# axiom_beta_plugin_module_TE0714_SDI_v0_8.net
KiCad netlist of a schematic drawn in EAGLE
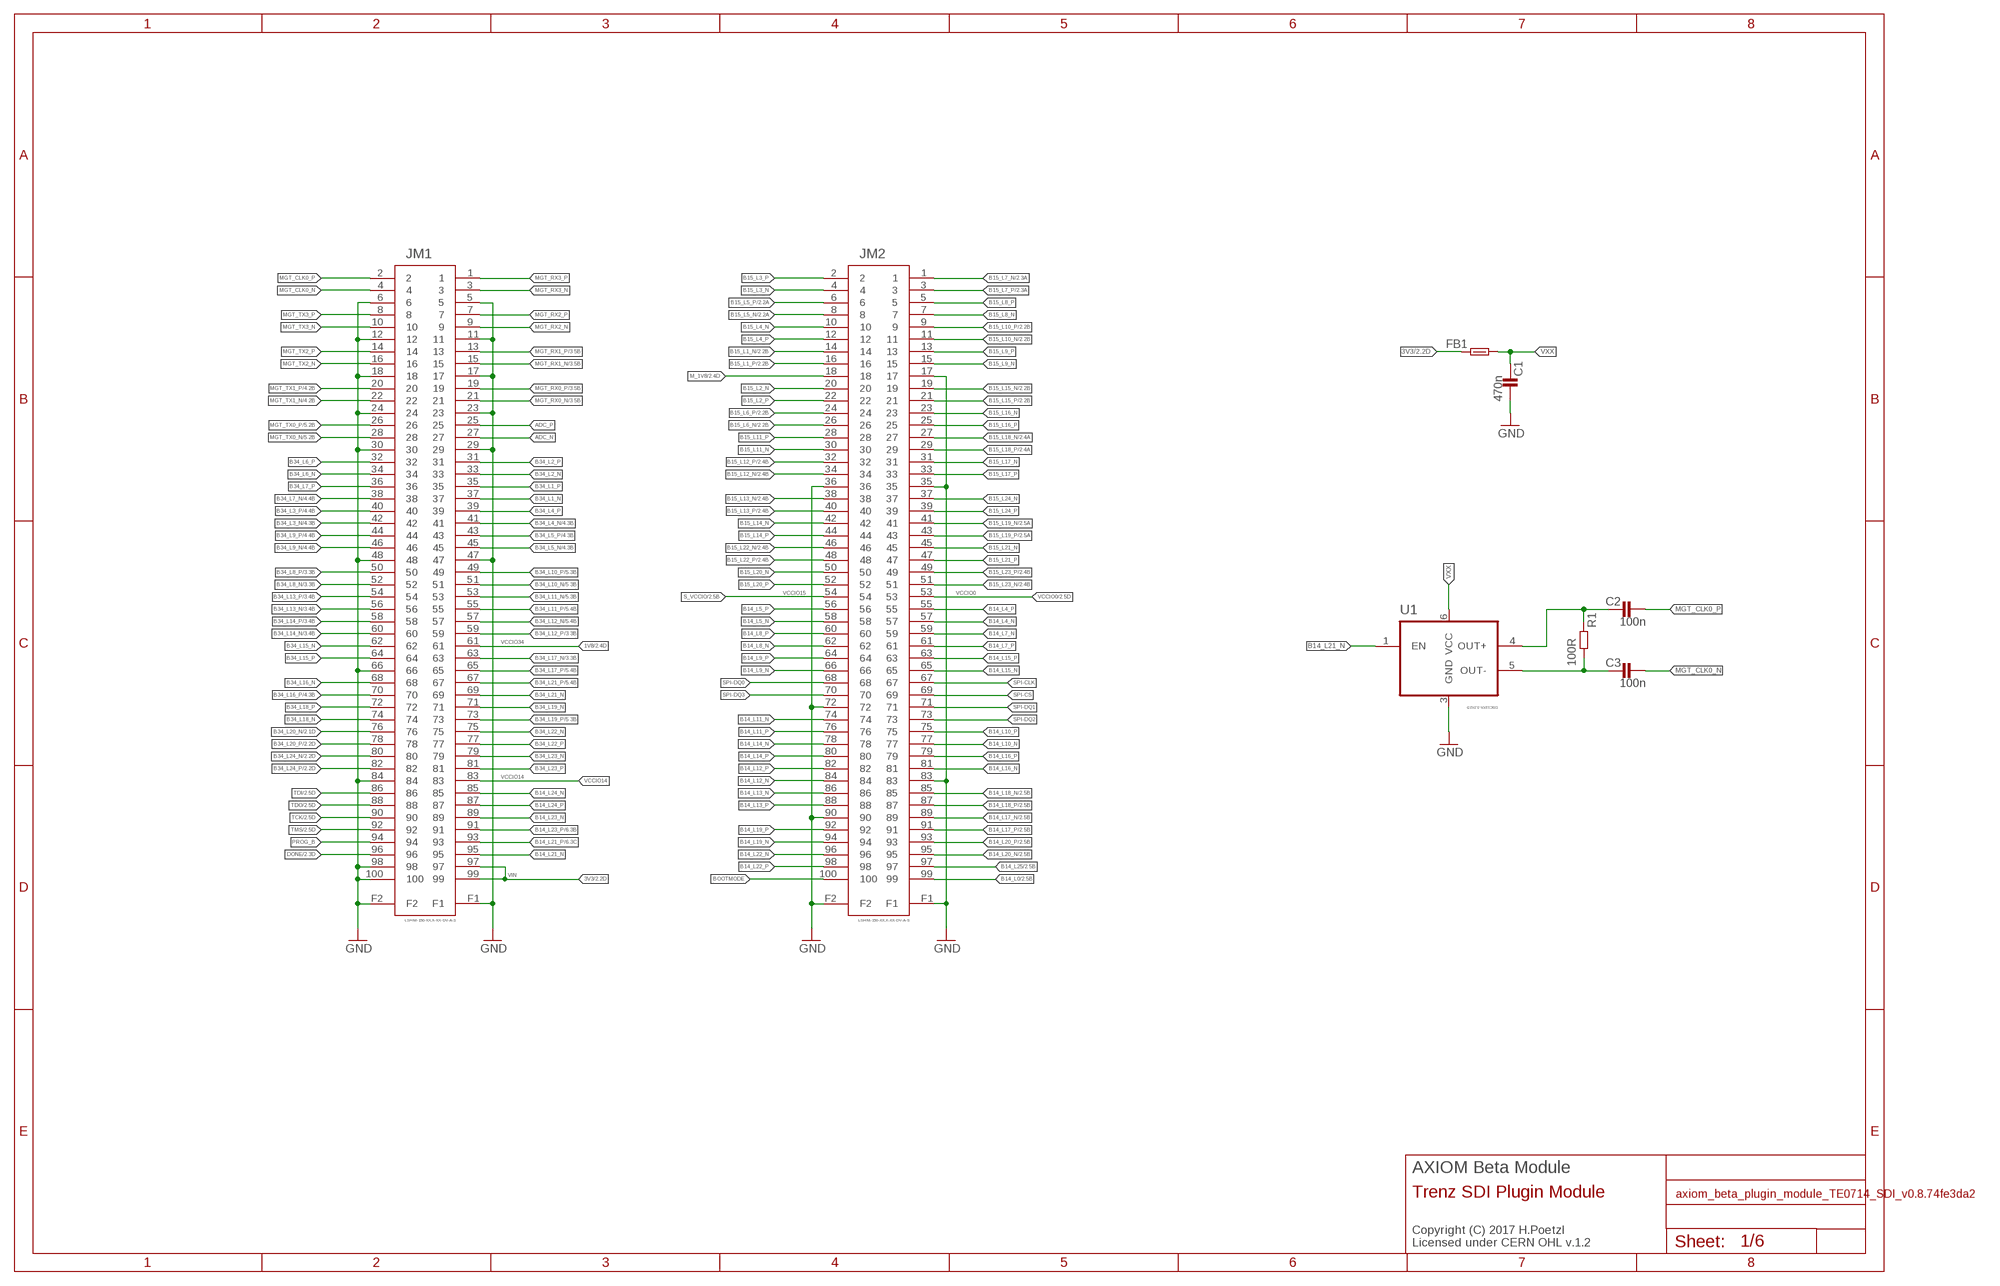
[diagram p0: schematic, sheet 1]
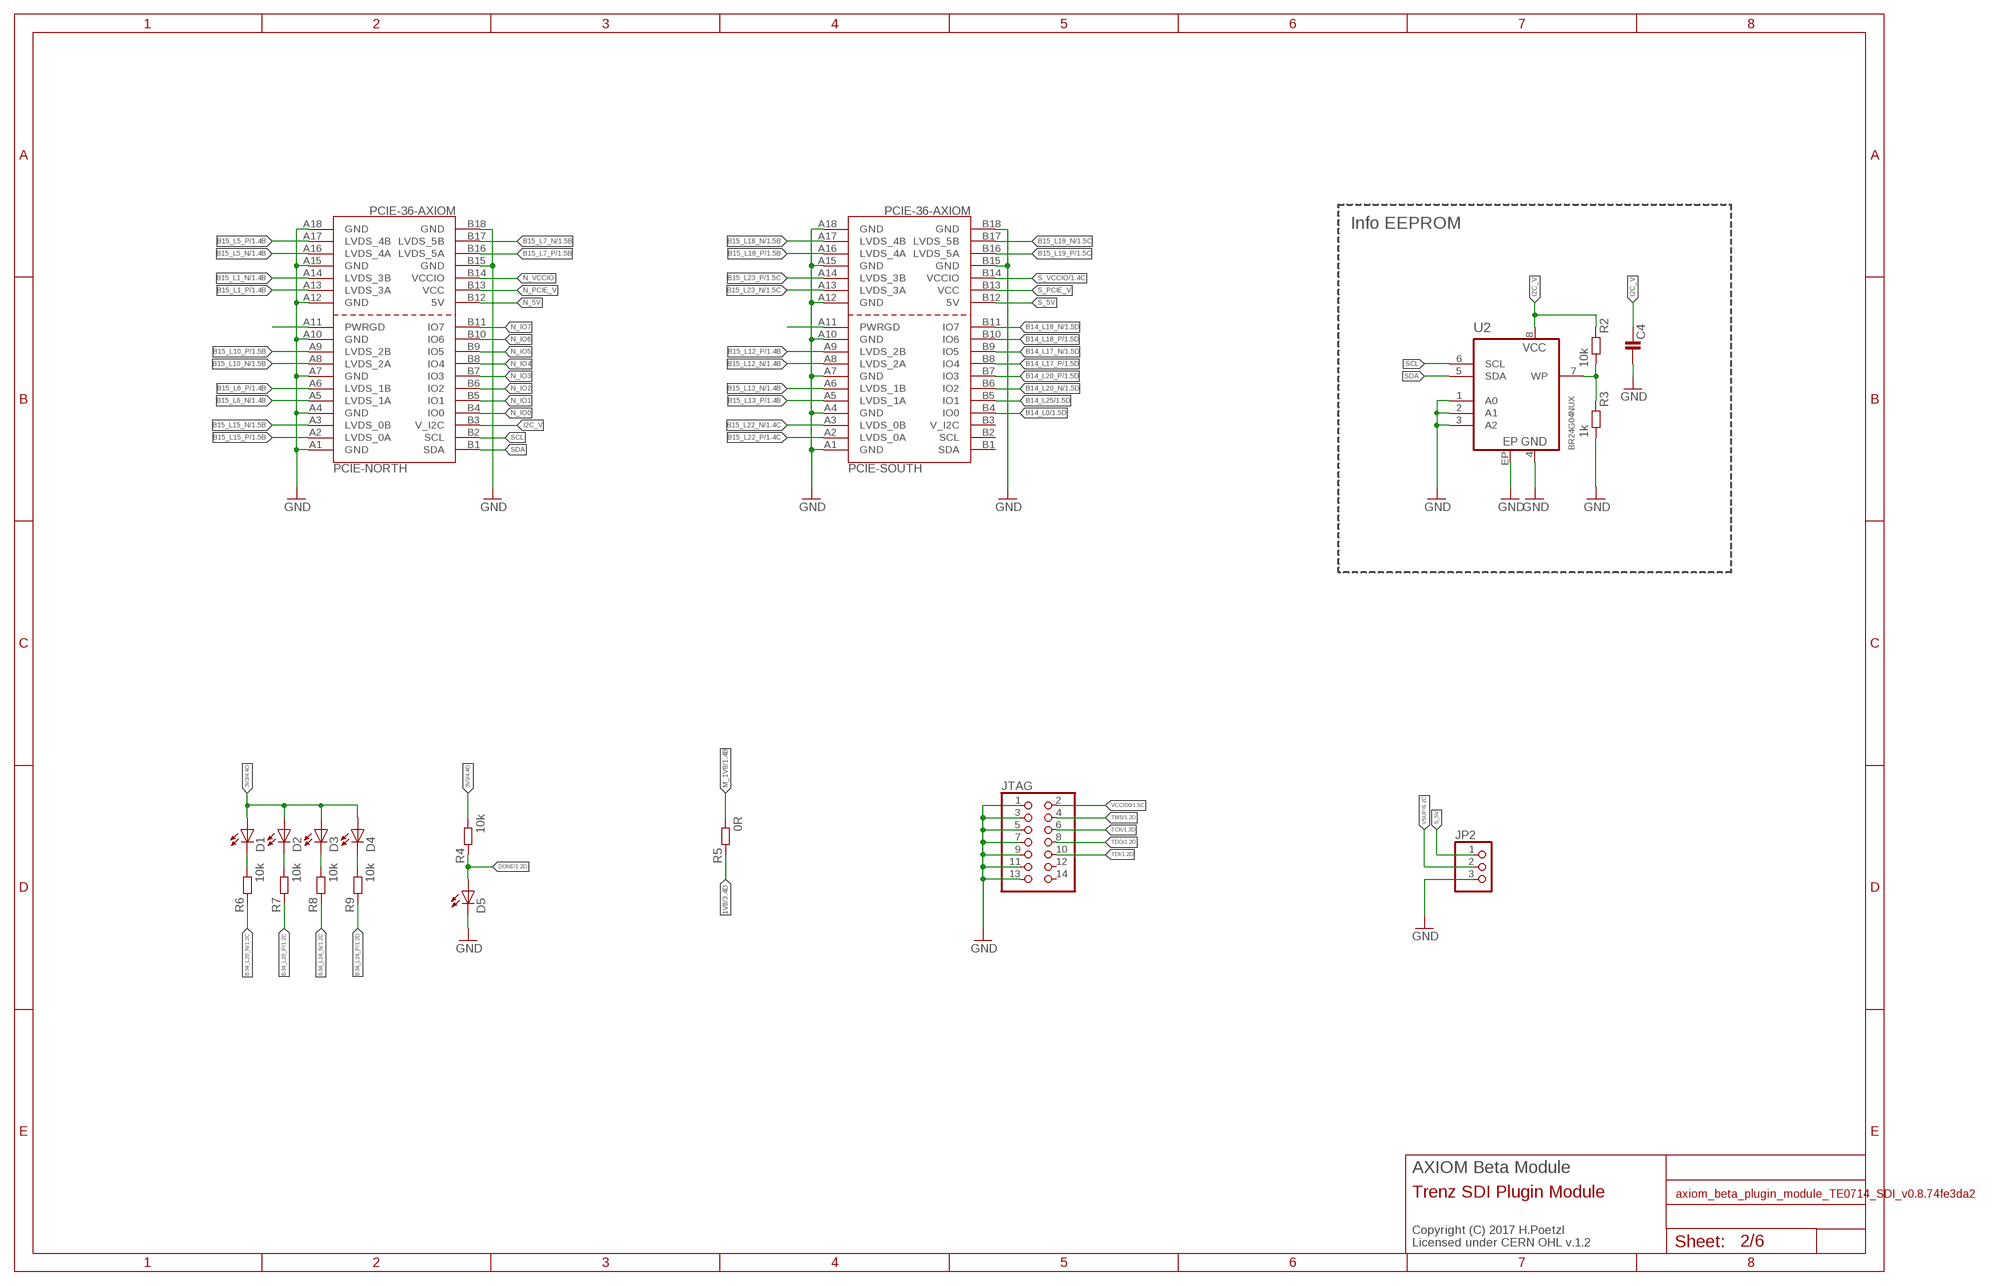
[diagram p1: schematic, sheet 2]
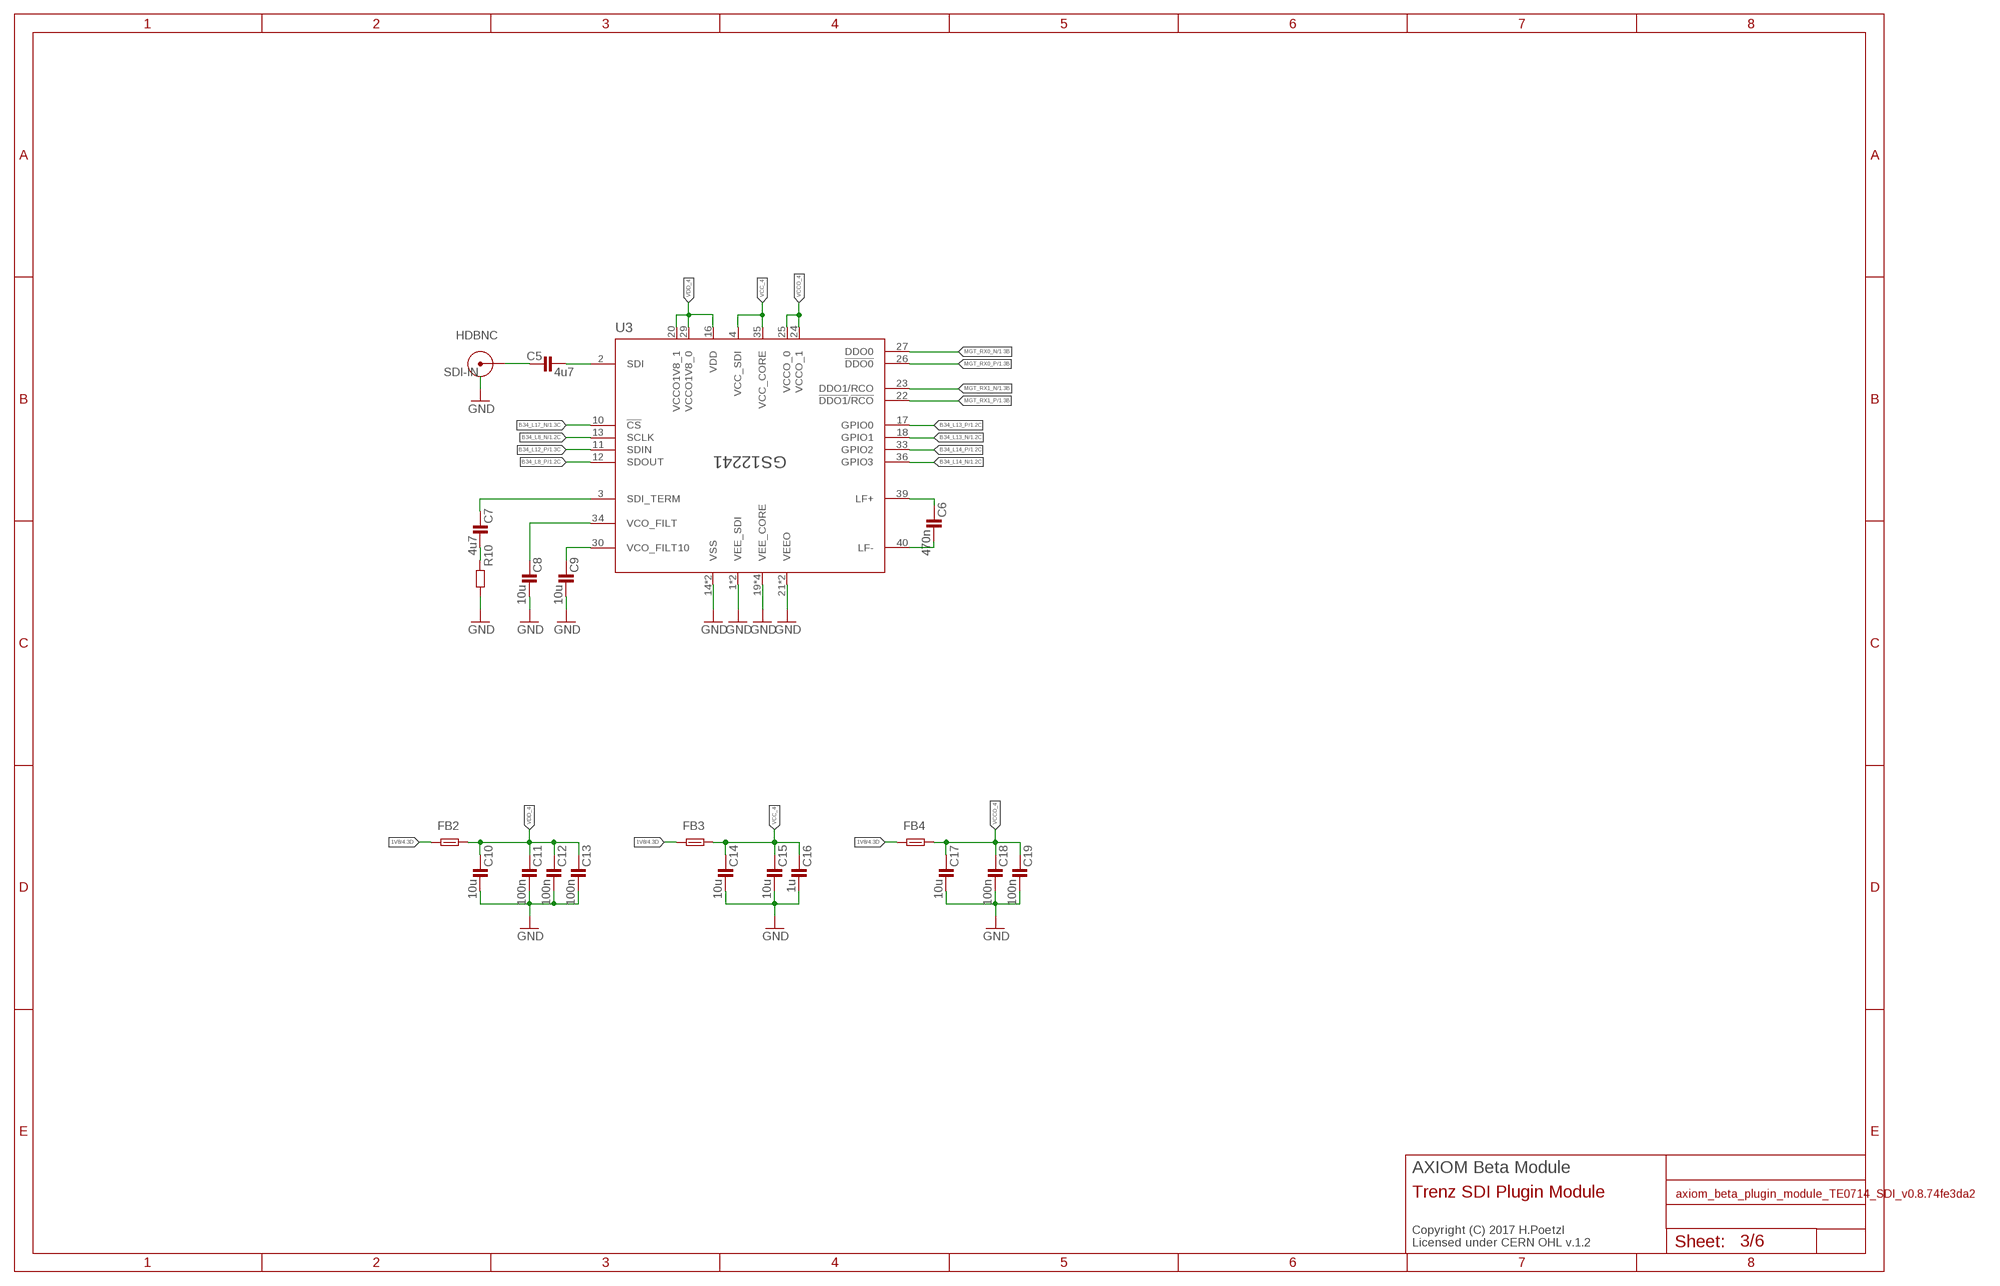
[diagram p2: schematic, sheet 3]
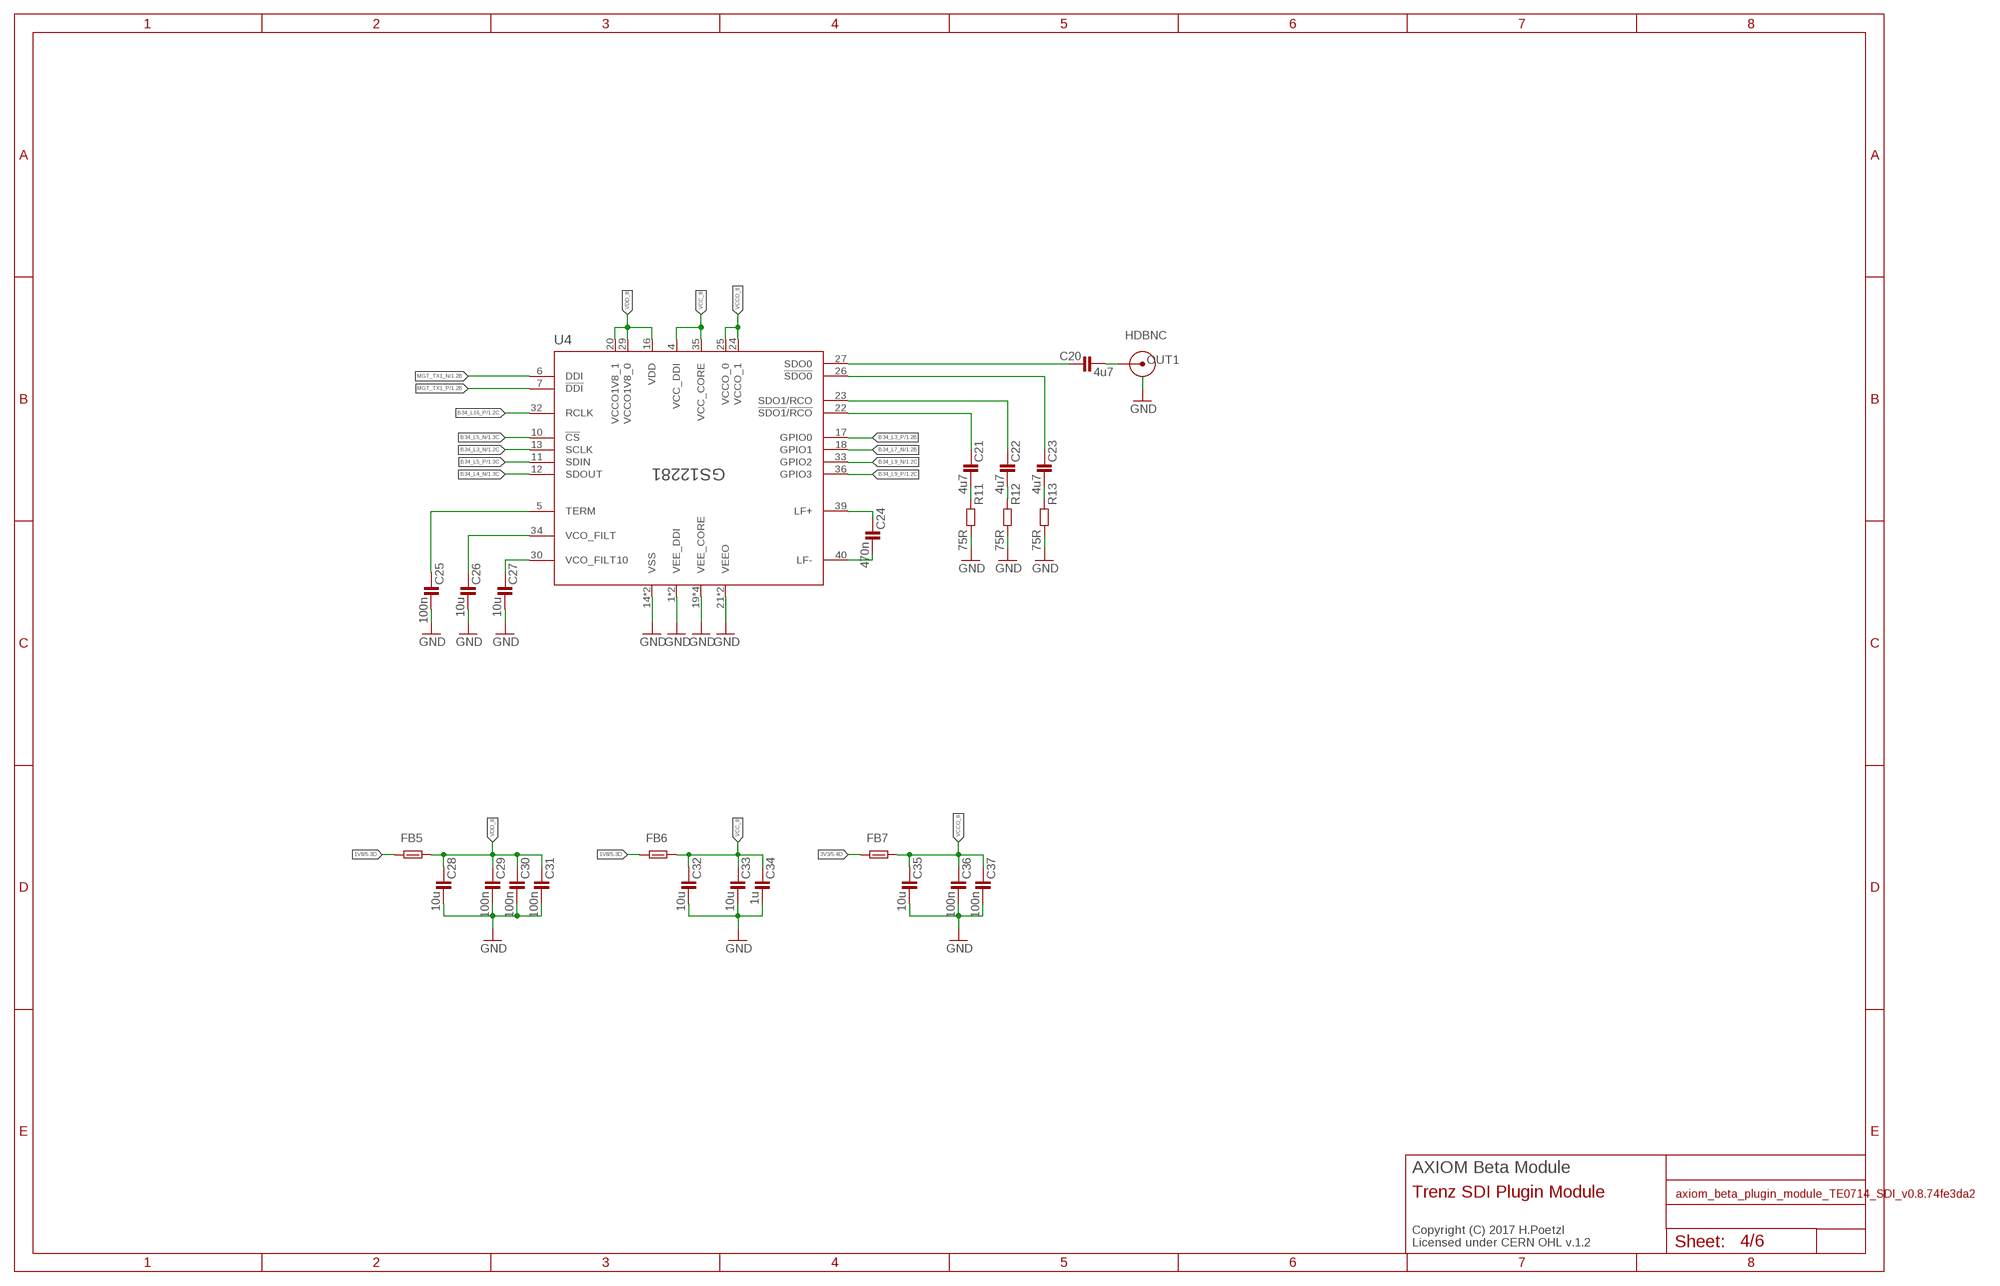
[diagram p3: schematic, sheet 4]
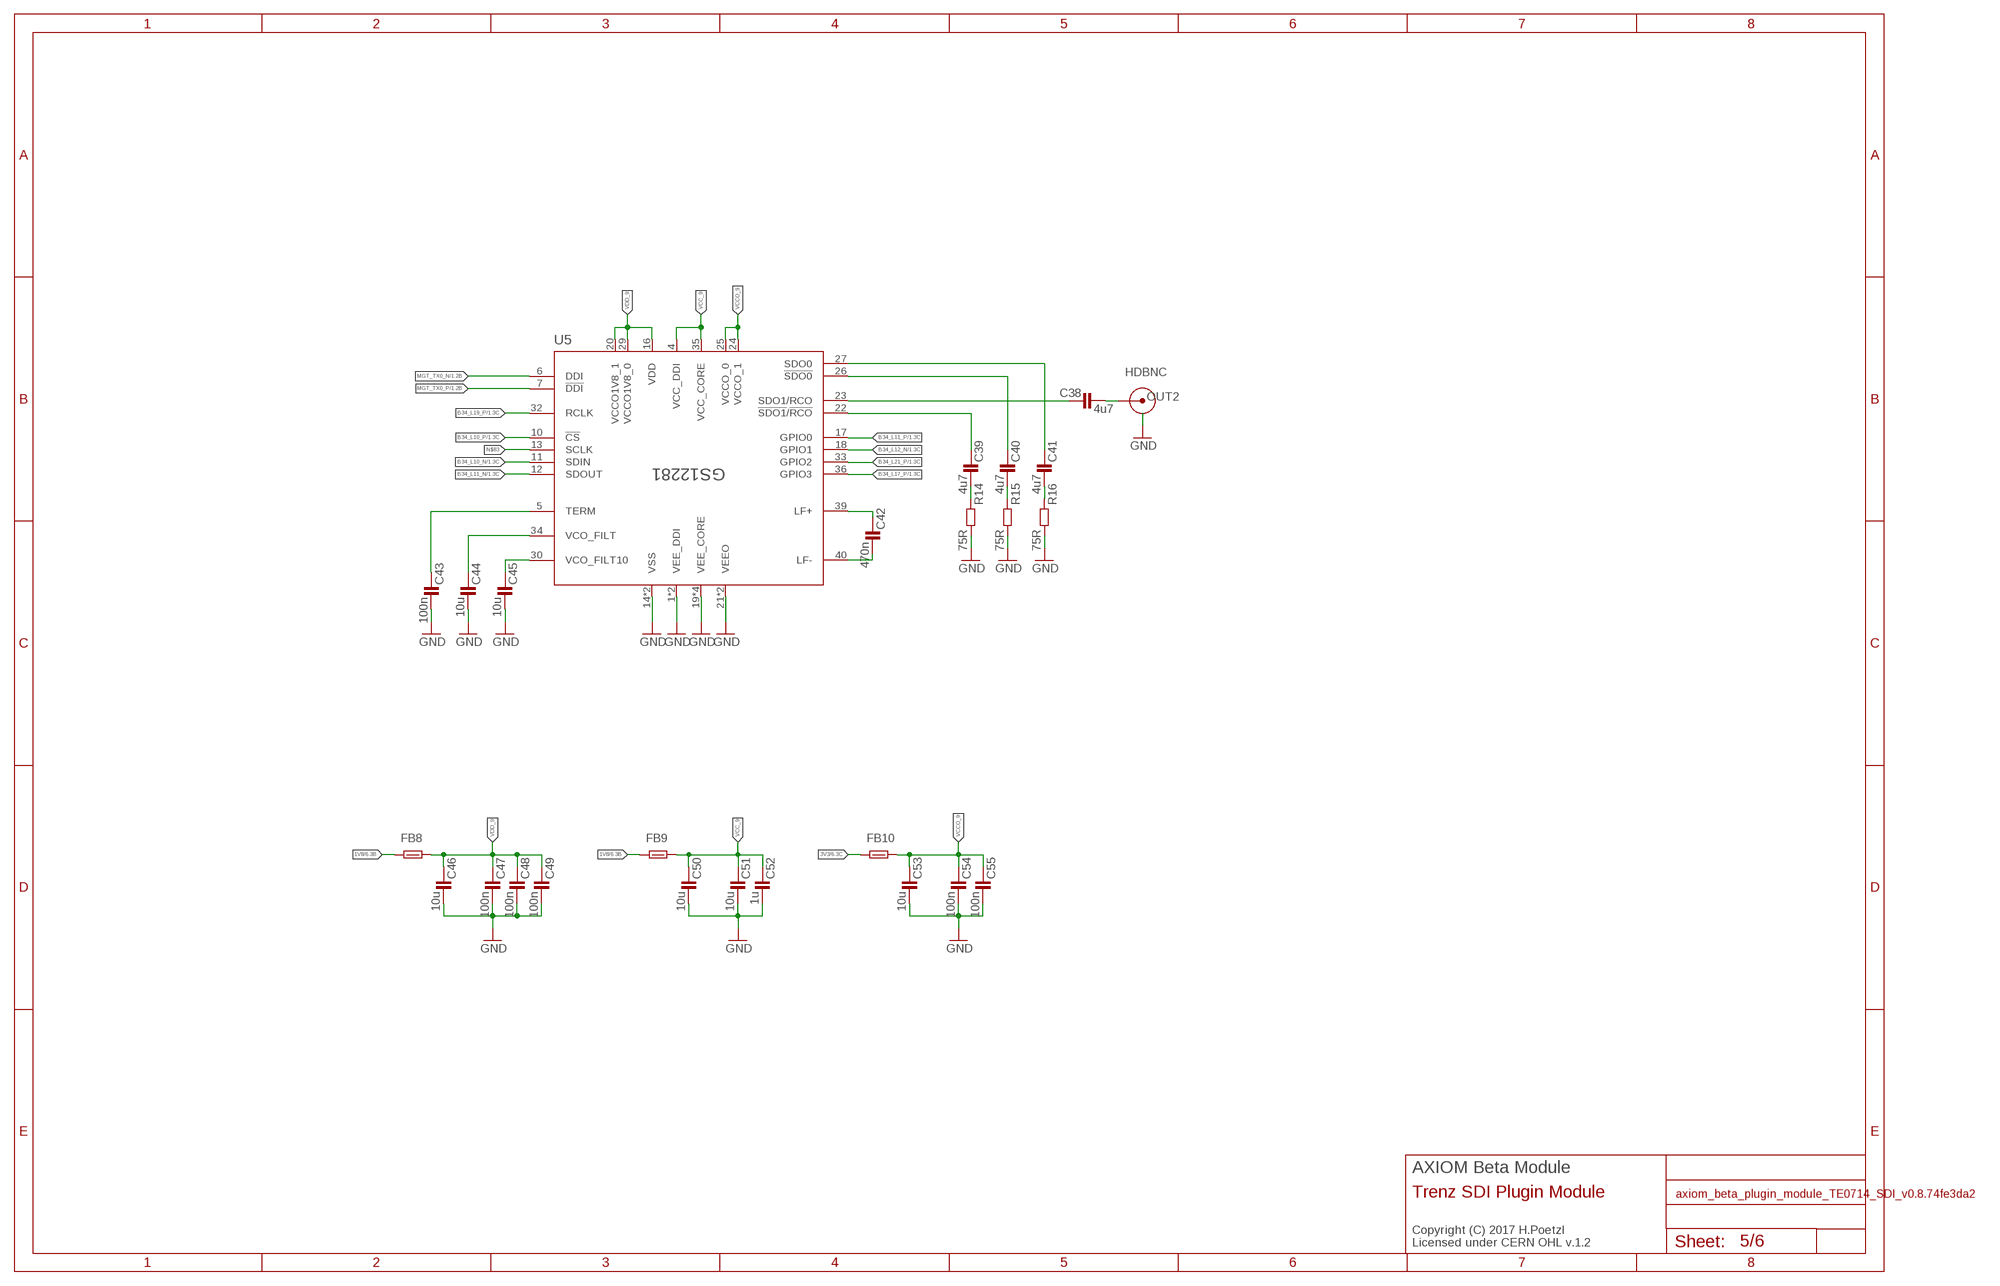
[diagram p4: schematic, sheet 5]
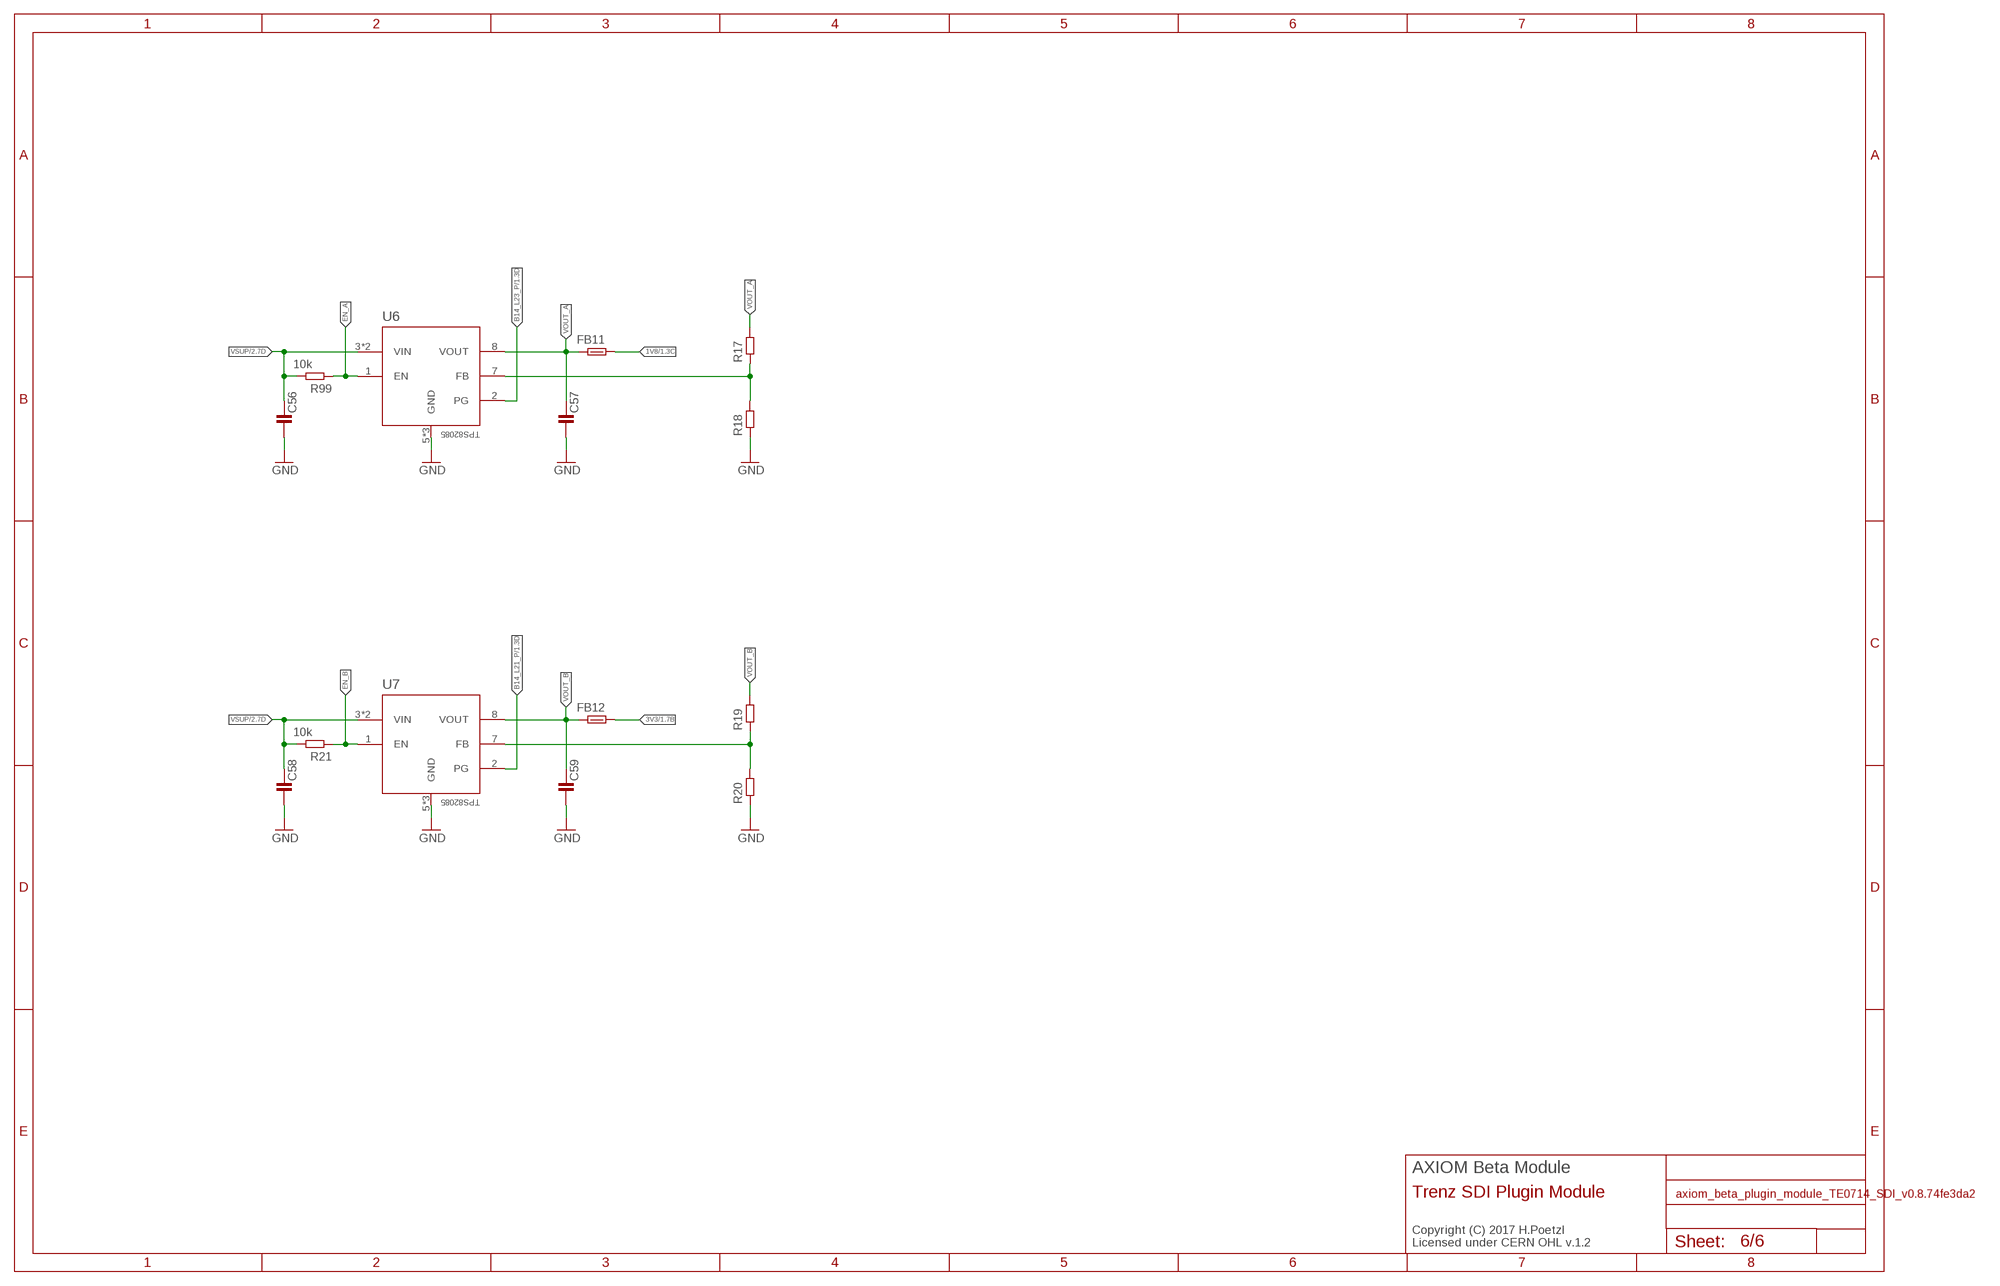
[diagram p5: schematic, sheet 6]

(export (version "E")
  (design (tool "Eeschema 10.0.6"))
  (components
    (comp (ref "C38")
      (value "4u7")
      (footprint "eagle-import:0402-C")
      (libsource (lib "eagle-import") (part "C0402-C"))
    )
    (comp (ref "C39")
      (value "4u7")
      (footprint "eagle-import:0402-C")
      (libsource (lib "eagle-import") (part "C0402-C"))
    )
    (comp (ref "C40")
      (value "4u7")
      (footprint "eagle-import:0402-C")
      (libsource (lib "eagle-import") (part "C0402-C"))
    )
    (comp (ref "C41")
      (value "4u7")
      (footprint "eagle-import:0402-C")
      (libsource (lib "eagle-import") (part "C0402-C"))
    )
    (comp (ref "C42")
      (value "470n")
      (footprint "eagle-import:0201-C")
      (libsource (lib "eagle-import") (part "C0201-C"))
    )
    (comp (ref "C43")
      (value "100n")
      (footprint "eagle-import:0201-C")
      (libsource (lib "eagle-import") (part "C0201-C"))
    )
    (comp (ref "C44")
      (value "10u")
      (footprint "eagle-import:0402-C")
      (libsource (lib "eagle-import") (part "C0402-C"))
    )
    (comp (ref "C45")
      (value "10u")
      (footprint "eagle-import:0402-C")
      (libsource (lib "eagle-import") (part "C0402-C"))
    )
    (comp (ref "C46")
      (value "10u")
      (footprint "eagle-import:0402-C")
      (libsource (lib "eagle-import") (part "C0402-C"))
    )
    (comp (ref "C47")
      (value "100n")
      (footprint "eagle-import:0201-C")
      (libsource (lib "eagle-import") (part "C0201-C"))
    )
    (comp (ref "C48")
      (value "100n")
      (footprint "eagle-import:0201-C")
      (libsource (lib "eagle-import") (part "C0201-C"))
    )
    (comp (ref "C49")
      (value "100n")
      (footprint "eagle-import:0201-C")
      (libsource (lib "eagle-import") (part "C0201-C"))
    )
    (comp (ref "C50")
      (value "10u")
      (footprint "eagle-import:0402-C")
      (libsource (lib "eagle-import") (part "C0402-C"))
    )
    (comp (ref "C51")
      (value "10u")
      (footprint "eagle-import:0402-C")
      (libsource (lib "eagle-import") (part "C0402-C"))
    )
    (comp (ref "C52")
      (value "1u")
      (footprint "eagle-import:0201-C")
      (libsource (lib "eagle-import") (part "C0201-C"))
    )
    (comp (ref "C53")
      (value "10u")
      (footprint "eagle-import:0402-C")
      (libsource (lib "eagle-import") (part "C0402-C"))
    )
    (comp (ref "C54")
      (value "100n")
      (footprint "eagle-import:0201-C")
      (libsource (lib "eagle-import") (part "C0201-C"))
    )
    (comp (ref "C55")
      (value "100n")
      (footprint "eagle-import:0201-C")
      (libsource (lib "eagle-import") (part "C0201-C"))
    )
    (comp (ref "FB8")
      (value "FB0402-C")
      (footprint "eagle-import:0402-C")
      (libsource (lib "eagle-import") (part "FB0402-C"))
    )
    (comp (ref "FB9")
      (value "FB0402-C")
      (footprint "eagle-import:0402-C")
      (libsource (lib "eagle-import") (part "FB0402-C"))
    )
    (comp (ref "FB10")
      (value "FB0402-C")
      (footprint "eagle-import:0402-C")
      (libsource (lib "eagle-import") (part "FB0402-C"))
    )
    (comp (ref "OUT2")
      (value "HDBNC")
      (footprint "eagle-import:HDBNC_EDGE_2SIDE")
      (libsource (lib "eagle-import") (part "HDBNC"))
    )
    (comp (ref "R14")
      (value "75R")
      (footprint "eagle-import:0201-C")
      (libsource (lib "eagle-import") (part "R0201-C"))
    )
    (comp (ref "R15")
      (value "75R")
      (footprint "eagle-import:0201-C")
      (libsource (lib "eagle-import") (part "R0201-C"))
    )
    (comp (ref "R16")
      (value "75R")
      (footprint "eagle-import:0201-C")
      (libsource (lib "eagle-import") (part "R0201-C"))
    )
    (comp (ref "U5")
      (value "GS12281")
      (footprint "eagle-import:UQFN40P600X400X100-41N")
      (libsource (lib "eagle-import") (part "GS12281"))
    )
    (comp (ref "C4")
      (value "C0402-B")
      (footprint "eagle-import:0402-B")
      (libsource (lib "eagle-import") (part "C0402-B"))
    )
    (comp (ref "D1")
      (value "LED")
      (footprint "eagle-import:CHIPLED_0603")
      (libsource (lib "eagle-import") (part "LED"))
    )
    (comp (ref "D2")
      (value "LED")
      (footprint "eagle-import:CHIPLED_0603")
      (libsource (lib "eagle-import") (part "LED"))
    )
    (comp (ref "D3")
      (value "LED")
      (footprint "eagle-import:CHIPLED_0603")
      (libsource (lib "eagle-import") (part "LED"))
    )
    (comp (ref "D4")
      (value "LED")
      (footprint "eagle-import:CHIPLED_0603")
      (libsource (lib "eagle-import") (part "LED"))
    )
    (comp (ref "D5")
      (value "LED")
      (footprint "eagle-import:CHIPLED_0603")
      (libsource (lib "eagle-import") (part "LED"))
    )
    (comp (ref "JP2")
      (value "PINHD-1X03_2.54-90°-S")
      (footprint "eagle-import:1X03_90-S")
      (libsource (lib "eagle-import") (part "PINHD-1X03_2.54-90°-S"))
    )
    (comp (ref "JTAG")
      (value "PINHD-2X07_2.00")
      (footprint "eagle-import:2X07M")
      (libsource (lib "eagle-import") (part "PINHD-2X07_2.00"))
    )
    (comp (ref "PCIE-NORTH")
      (value "PCIE-36-AXIOM")
      (footprint "eagle-import:PCIE-36-AXIOM")
      (libsource (lib "eagle-import") (part "PCIE-36-AXIOM"))
    )
    (comp (ref "PCIE-SOUTH")
      (value "PCIE-36-AXIOM")
      (footprint "eagle-import:PCIE-36-AXIOM")
      (libsource (lib "eagle-import") (part "PCIE-36-AXIOM"))
    )
    (comp (ref "R2")
      (value "10k")
      (footprint "eagle-import:0402-B")
      (libsource (lib "eagle-import") (part "R0402-B"))
    )
    (comp (ref "R3")
      (value "1k")
      (footprint "eagle-import:0402-B")
      (libsource (lib "eagle-import") (part "R0402-B"))
    )
    (comp (ref "R4")
      (value "10k")
      (footprint "eagle-import:0402-C")
      (libsource (lib "eagle-import") (part "R0402-C"))
    )
    (comp (ref "R5")
      (value "0R")
      (footprint "eagle-import:0402-C")
      (libsource (lib "eagle-import") (part "R0402-C"))
    )
    (comp (ref "R6")
      (value "10k")
      (footprint "eagle-import:0402-C")
      (libsource (lib "eagle-import") (part "R0402-C"))
    )
    (comp (ref "R7")
      (value "10k")
      (footprint "eagle-import:0402-C")
      (libsource (lib "eagle-import") (part "R0402-C"))
    )
    (comp (ref "R8")
      (value "10k")
      (footprint "eagle-import:0402-C")
      (libsource (lib "eagle-import") (part "R0402-C"))
    )
    (comp (ref "R9")
      (value "10k")
      (footprint "eagle-import:0402-C")
      (libsource (lib "eagle-import") (part "R0402-C"))
    )
    (comp (ref "U2")
      (value "BR24G04NUX")
      (footprint "eagle-import:DFN200X300X100-9N")
      (libsource (lib "eagle-import") (part "BR24G04NUX"))
    )
    (comp (ref "C5")
      (value "4u7")
      (footprint "eagle-import:0402-C")
      (libsource (lib "eagle-import") (part "C0402-C"))
    )
    (comp (ref "C6")
      (value "470n")
      (footprint "eagle-import:0201-C")
      (libsource (lib "eagle-import") (part "C0201-C"))
    )
    (comp (ref "C7")
      (value "4u7")
      (footprint "eagle-import:0402-C")
      (libsource (lib "eagle-import") (part "C0402-C"))
    )
    (comp (ref "C8")
      (value "10u")
      (footprint "eagle-import:0201-C")
      (libsource (lib "eagle-import") (part "C0201-C"))
    )
    (comp (ref "C9")
      (value "10u")
      (footprint "eagle-import:0402-C")
      (libsource (lib "eagle-import") (part "C0402-C"))
    )
    (comp (ref "C10")
      (value "10u")
      (footprint "eagle-import:0402-C")
      (libsource (lib "eagle-import") (part "C0402-C"))
    )
    (comp (ref "C11")
      (value "100n")
      (footprint "eagle-import:0201-C")
      (libsource (lib "eagle-import") (part "C0201-C"))
    )
    (comp (ref "C12")
      (value "100n")
      (footprint "eagle-import:0201-C")
      (libsource (lib "eagle-import") (part "C0201-C"))
    )
    (comp (ref "C13")
      (value "100n")
      (footprint "eagle-import:0201-C")
      (libsource (lib "eagle-import") (part "C0201-C"))
    )
    (comp (ref "C14")
      (value "10u")
      (footprint "eagle-import:0402-C")
      (libsource (lib "eagle-import") (part "C0402-C"))
    )
    (comp (ref "C15")
      (value "10u")
      (footprint "eagle-import:0402-C")
      (libsource (lib "eagle-import") (part "C0402-C"))
    )
    (comp (ref "C16")
      (value "1u")
      (footprint "eagle-import:0201-C")
      (libsource (lib "eagle-import") (part "C0201-C"))
    )
    (comp (ref "C17")
      (value "10u")
      (footprint "eagle-import:0402-C")
      (libsource (lib "eagle-import") (part "C0402-C"))
    )
    (comp (ref "C18")
      (value "100n")
      (footprint "eagle-import:0201-C")
      (libsource (lib "eagle-import") (part "C0201-C"))
    )
    (comp (ref "C19")
      (value "100n")
      (footprint "eagle-import:0201-C")
      (libsource (lib "eagle-import") (part "C0201-C"))
    )
    (comp (ref "FB2")
      (value "FB0402-C")
      (footprint "eagle-import:0402-C")
      (libsource (lib "eagle-import") (part "FB0402-C"))
    )
    (comp (ref "FB3")
      (value "FB0402-C")
      (footprint "eagle-import:0402-C")
      (libsource (lib "eagle-import") (part "FB0402-C"))
    )
    (comp (ref "FB4")
      (value "FB0402-C")
      (footprint "eagle-import:0402-C")
      (libsource (lib "eagle-import") (part "FB0402-C"))
    )
    (comp (ref "R10")
      (value "R0201-C")
      (footprint "eagle-import:0201-C")
      (libsource (lib "eagle-import") (part "R0201-C"))
    )
    (comp (ref "SDI-IN")
      (value "HDBNC")
      (footprint "eagle-import:HDBNC_EDGE_2SIDE")
      (libsource (lib "eagle-import") (part "HDBNC"))
    )
    (comp (ref "U3")
      (value "GS12241")
      (footprint "eagle-import:UQFN40P600X400X100-41N")
      (libsource (lib "eagle-import") (part "GS12241"))
    )
    (comp (ref "C20")
      (value "4u7")
      (footprint "eagle-import:0402-C")
      (libsource (lib "eagle-import") (part "C0402-C"))
    )
    (comp (ref "C21")
      (value "4u7")
      (footprint "eagle-import:0402-C")
      (libsource (lib "eagle-import") (part "C0402-C"))
    )
    (comp (ref "C22")
      (value "4u7")
      (footprint "eagle-import:0402-C")
      (libsource (lib "eagle-import") (part "C0402-C"))
    )
    (comp (ref "C23")
      (value "4u7")
      (footprint "eagle-import:0402-C")
      (libsource (lib "eagle-import") (part "C0402-C"))
    )
    (comp (ref "C24")
      (value "470n")
      (footprint "eagle-import:0201-C")
      (libsource (lib "eagle-import") (part "C0201-C"))
    )
    (comp (ref "C25")
      (value "100n")
      (footprint "eagle-import:0201-C")
      (libsource (lib "eagle-import") (part "C0201-C"))
    )
    (comp (ref "C26")
      (value "10u")
      (footprint "eagle-import:0201-C")
      (libsource (lib "eagle-import") (part "C0201-C"))
    )
    (comp (ref "C27")
      (value "10u")
      (footprint "eagle-import:0402-C")
      (libsource (lib "eagle-import") (part "C0402-C"))
    )
    (comp (ref "C28")
      (value "10u")
      (footprint "eagle-import:0402-C")
      (libsource (lib "eagle-import") (part "C0402-C"))
    )
    (comp (ref "C29")
      (value "100n")
      (footprint "eagle-import:0201-C")
      (libsource (lib "eagle-import") (part "C0201-C"))
    )
    (comp (ref "C30")
      (value "100n")
      (footprint "eagle-import:0201-C")
      (libsource (lib "eagle-import") (part "C0201-C"))
    )
    (comp (ref "C31")
      (value "100n")
      (footprint "eagle-import:0201-C")
      (libsource (lib "eagle-import") (part "C0201-C"))
    )
    (comp (ref "C32")
      (value "10u")
      (footprint "eagle-import:0402-C")
      (libsource (lib "eagle-import") (part "C0402-C"))
    )
    (comp (ref "C33")
      (value "10u")
      (footprint "eagle-import:0402-C")
      (libsource (lib "eagle-import") (part "C0402-C"))
    )
    (comp (ref "C34")
      (value "1u")
      (footprint "eagle-import:0201-C")
      (libsource (lib "eagle-import") (part "C0201-C"))
    )
    (comp (ref "C35")
      (value "10u")
      (footprint "eagle-import:0402-C")
      (libsource (lib "eagle-import") (part "C0402-C"))
    )
    (comp (ref "C36")
      (value "100n")
      (footprint "eagle-import:0201-C")
      (libsource (lib "eagle-import") (part "C0201-C"))
    )
    (comp (ref "C37")
      (value "100n")
      (footprint "eagle-import:0201-C")
      (libsource (lib "eagle-import") (part "C0201-C"))
    )
    (comp (ref "FB5")
      (value "FB0402-C")
      (footprint "eagle-import:0402-C")
      (libsource (lib "eagle-import") (part "FB0402-C"))
    )
    (comp (ref "FB6")
      (value "FB0402-C")
      (footprint "eagle-import:0402-C")
      (libsource (lib "eagle-import") (part "FB0402-C"))
    )
    (comp (ref "FB7")
      (value "FB0402-C")
      (footprint "eagle-import:0402-C")
      (libsource (lib "eagle-import") (part "FB0402-C"))
    )
    (comp (ref "OUT1")
      (value "HDBNC")
      (footprint "eagle-import:HDBNC_EDGE_2SIDE")
      (libsource (lib "eagle-import") (part "HDBNC"))
    )
    (comp (ref "R11")
      (value "75R")
      (footprint "eagle-import:0201-C")
      (libsource (lib "eagle-import") (part "R0201-C"))
    )
    (comp (ref "R12")
      (value "75R")
      (footprint "eagle-import:0201-C")
      (libsource (lib "eagle-import") (part "R0201-C"))
    )
    (comp (ref "R13")
      (value "75R")
      (footprint "eagle-import:0201-C")
      (libsource (lib "eagle-import") (part "R0201-C"))
    )
    (comp (ref "U4")
      (value "GS12281")
      (footprint "eagle-import:UQFN40P600X400X100-41N")
      (libsource (lib "eagle-import") (part "GS12281"))
    )
    (comp (ref "C1")
      (value "470n")
      (footprint "eagle-import:0402-C")
      (libsource (lib "eagle-import") (part "C0402-C"))
    )
    (comp (ref "C2")
      (value "100n")
      (footprint "eagle-import:0201-C")
      (libsource (lib "eagle-import") (part "C0201-C"))
    )
    (comp (ref "C3")
      (value "100n")
      (footprint "eagle-import:0201-C")
      (libsource (lib "eagle-import") (part "C0201-C"))
    )
    (comp (ref "FB1")
      (value "FB0402-C")
      (footprint "eagle-import:0402-C")
      (libsource (lib "eagle-import") (part "FB0402-C"))
    )
    (comp (ref "JM1")
      (value "LSHM-150-XX.X-XX-DV-A-S")
      (footprint "eagle-import:LSHM-150-XX.X-XX-DV-A-S")
      (libsource (lib "eagle-import") (part "LSHM-150-XX.X-XX-DV-A-S"))
    )
    (comp (ref "JM2")
      (value "LSHM-150-XX.X-XX-DV-A-S")
      (footprint "eagle-import:LSHM-150-XX.X-XX-DV-A-S")
      (libsource (lib "eagle-import") (part "LSHM-150-XX.X-XX-DV-A-S"))
    )
    (comp (ref "R1")
      (value "100R")
      (footprint "eagle-import:0201-C")
      (libsource (lib "eagle-import") (part "R0201-C"))
    )
    (comp (ref "U1")
      (value "DSC11XX-3.2X2.5")
      (footprint "eagle-import:3.2X2.5")
      (libsource (lib "eagle-import") (part "DSC11XX-3.2X2.5"))
    )
    (comp (ref "C56")
      (value "C0603-C")
      (footprint "eagle-import:0603-C")
      (libsource (lib "eagle-import") (part "C0603-C"))
    )
    (comp (ref "C57")
      (value "C0603-C")
      (footprint "eagle-import:0603-C")
      (libsource (lib "eagle-import") (part "C0603-C"))
    )
    (comp (ref "C58")
      (value "C0603-C")
      (footprint "eagle-import:0603-C")
      (libsource (lib "eagle-import") (part "C0603-C"))
    )
    (comp (ref "C59")
      (value "C0603-C")
      (footprint "eagle-import:0603-C")
      (libsource (lib "eagle-import") (part "C0603-C"))
    )
    (comp (ref "FB11")
      (value "FB0603-C")
      (footprint "eagle-import:0603-C")
      (libsource (lib "eagle-import") (part "FB0603-C"))
    )
    (comp (ref "FB12")
      (value "FB0603-C")
      (footprint "eagle-import:0603-C")
      (libsource (lib "eagle-import") (part "FB0603-C"))
    )
    (comp (ref "R17")
      (value "R0201-C")
      (footprint "eagle-import:0201-C")
      (libsource (lib "eagle-import") (part "R0201-C"))
    )
    (comp (ref "R18")
      (value "R0201-C")
      (footprint "eagle-import:0201-C")
      (libsource (lib "eagle-import") (part "R0201-C"))
    )
    (comp (ref "R19")
      (value "R0201-C")
      (footprint "eagle-import:0201-C")
      (libsource (lib "eagle-import") (part "R0201-C"))
    )
    (comp (ref "R20")
      (value "R0201-C")
      (footprint "eagle-import:0201-C")
      (libsource (lib "eagle-import") (part "R0201-C"))
    )
    (comp (ref "R21")
      (value "10k")
      (footprint "eagle-import:0201-C")
      (libsource (lib "eagle-import") (part "R0201-C"))
    )
    (comp (ref "R99")
      (value "10k")
      (footprint "eagle-import:0201-C")
      (libsource (lib "eagle-import") (part "R0201-C"))
    )
    (comp (ref "U6")
      (value "TPS82085")
      (footprint "eagle-import:MICROSIP")
      (libsource (lib "eagle-import") (part "TPS82085"))
    )
    (comp (ref "U7")
      (value "TPS82085")
      (footprint "eagle-import:MICROSIP")
      (libsource (lib "eagle-import") (part "TPS82085"))
    )
  )
  (nets
    (net (code "1") (name "1V8") (class "Default")
      (node (ref "FB11") (pin "2") (pinfunction "2_2") (pintype "passive"))
      (node (ref "FB2") (pin "1") (pinfunction "1_1") (pintype "passive"))
      (node (ref "FB3") (pin "1") (pinfunction "1_1") (pintype "passive"))
      (node (ref "FB4") (pin "1") (pinfunction "1_1") (pintype "passive"))
      (node (ref "FB5") (pin "1") (pinfunction "1_1") (pintype "passive"))
      (node (ref "FB6") (pin "1") (pinfunction "1_1") (pintype "passive"))
      (node (ref "FB8") (pin "1") (pinfunction "1_1") (pintype "passive"))
      (node (ref "FB9") (pin "1") (pinfunction "1_1") (pintype "passive"))
      (node (ref "JM1") (pin "61") (pinfunction "61_61") (pintype "bidirectional"))
      (node (ref "R5") (pin "1") (pinfunction "1_1") (pintype "passive"))
    )
    (net (code "2") (name "3V3") (class "Default")
      (node (ref "D1") (pin "A") (pinfunction "A_A") (pintype "passive"))
      (node (ref "D2") (pin "A") (pinfunction "A_A") (pintype "passive"))
      (node (ref "D3") (pin "A") (pinfunction "A_A") (pintype "passive"))
      (node (ref "D4") (pin "A") (pinfunction "A_A") (pintype "passive"))
      (node (ref "FB1") (pin "1") (pinfunction "1_1") (pintype "passive"))
      (node (ref "FB10") (pin "1") (pinfunction "1_1") (pintype "passive"))
      (node (ref "FB12") (pin "2") (pinfunction "2_2") (pintype "passive"))
      (node (ref "FB7") (pin "1") (pinfunction "1_1") (pintype "passive"))
      (node (ref "JM1") (pin "97") (pinfunction "97_97") (pintype "bidirectional"))
      (node (ref "JM1") (pin "99") (pinfunction "99_99") (pintype "bidirectional"))
      (node (ref "R4") (pin "2") (pinfunction "2_2") (pintype "passive"))
    )
    (net (code "3") (name "ADC_N") (class "Default")
      (node (ref "JM1") (pin "27") (pinfunction "27_27") (pintype "bidirectional"))
    )
    (net (code "4") (name "ADC_P") (class "Default")
      (node (ref "JM1") (pin "25") (pinfunction "25_25") (pintype "bidirectional"))
    )
    (net (code "5") (name "B14_L0") (class "Default")
      (node (ref "JM2") (pin "99") (pinfunction "99_99") (pintype "bidirectional"))
      (node (ref "PCIE-SOUTH") (pin "B4") (pinfunction "IO0_B4") (pintype "passive"))
    )
    (net (code "6") (name "B14_L4_N") (class "Default")
      (node (ref "JM2") (pin "57") (pinfunction "57_57") (pintype "bidirectional"))
    )
    (net (code "7") (name "B14_L4_P") (class "Default")
      (node (ref "JM2") (pin "55") (pinfunction "55_55") (pintype "bidirectional"))
    )
    (net (code "8") (name "B14_L5_N") (class "Default")
      (node (ref "JM2") (pin "58") (pinfunction "58_58") (pintype "bidirectional"))
    )
    (net (code "9") (name "B14_L5_P") (class "Default")
      (node (ref "JM2") (pin "56") (pinfunction "56_56") (pintype "bidirectional"))
    )
    (net (code "10") (name "B14_L7_N") (class "Default")
      (node (ref "JM2") (pin "59") (pinfunction "59_59") (pintype "bidirectional"))
    )
    (net (code "11") (name "B14_L7_P") (class "Default")
      (node (ref "JM2") (pin "61") (pinfunction "61_61") (pintype "bidirectional"))
    )
    (net (code "12") (name "B14_L8_N") (class "Default")
      (node (ref "JM2") (pin "62") (pinfunction "62_62") (pintype "bidirectional"))
    )
    (net (code "13") (name "B14_L8_P") (class "Default")
      (node (ref "JM2") (pin "60") (pinfunction "60_60") (pintype "bidirectional"))
    )
    (net (code "14") (name "B14_L9_N") (class "Default")
      (node (ref "JM2") (pin "66") (pinfunction "66_66") (pintype "bidirectional"))
    )
    (net (code "15") (name "B14_L9_P") (class "Default")
      (node (ref "JM2") (pin "64") (pinfunction "64_64") (pintype "bidirectional"))
    )
    (net (code "16") (name "B14_L10_N") (class "Default")
      (node (ref "JM2") (pin "77") (pinfunction "77_77") (pintype "bidirectional"))
    )
    (net (code "17") (name "B14_L10_P") (class "Default")
      (node (ref "JM2") (pin "75") (pinfunction "75_75") (pintype "bidirectional"))
    )
    (net (code "18") (name "B14_L11_N") (class "Default")
      (node (ref "JM2") (pin "74") (pinfunction "74_74") (pintype "bidirectional"))
    )
    (net (code "19") (name "B14_L11_P") (class "Default")
      (node (ref "JM2") (pin "76") (pinfunction "76_76") (pintype "bidirectional"))
    )
    (net (code "20") (name "B14_L12_N") (class "Default")
      (node (ref "JM2") (pin "84") (pinfunction "84_84") (pintype "bidirectional"))
    )
    (net (code "21") (name "B14_L12_P") (class "Default")
      (node (ref "JM2") (pin "82") (pinfunction "82_82") (pintype "bidirectional"))
    )
    (net (code "22") (name "B14_L13_N") (class "Default")
      (node (ref "JM2") (pin "86") (pinfunction "86_86") (pintype "bidirectional"))
    )
    (net (code "23") (name "B14_L13_P") (class "Default")
      (node (ref "JM2") (pin "88") (pinfunction "88_88") (pintype "bidirectional"))
    )
    (net (code "24") (name "B14_L14_N") (class "Default")
      (node (ref "JM2") (pin "78") (pinfunction "78_78") (pintype "bidirectional"))
    )
    (net (code "25") (name "B14_L14_P") (class "Default")
      (node (ref "JM2") (pin "80") (pinfunction "80_80") (pintype "bidirectional"))
    )
    (net (code "26") (name "B14_L15_N") (class "Default")
      (node (ref "JM2") (pin "65") (pinfunction "65_65") (pintype "bidirectional"))
    )
    (net (code "27") (name "B14_L15_P") (class "Default")
      (node (ref "JM2") (pin "63") (pinfunction "63_63") (pintype "bidirectional"))
    )
    (net (code "28") (name "B14_L16_N") (class "Default")
      (node (ref "JM2") (pin "81") (pinfunction "81_81") (pintype "bidirectional"))
    )
    (net (code "29") (name "B14_L16_P") (class "Default")
      (node (ref "JM2") (pin "79") (pinfunction "79_79") (pintype "bidirectional"))
    )
    (net (code "30") (name "B14_L17_N") (class "Default")
      (node (ref "JM2") (pin "89") (pinfunction "89_89") (pintype "bidirectional"))
      (node (ref "PCIE-SOUTH") (pin "B9") (pinfunction "IO5_B9") (pintype "passive"))
    )
    (net (code "31") (name "B14_L17_P") (class "Default")
      (node (ref "JM2") (pin "91") (pinfunction "91_91") (pintype "bidirectional"))
      (node (ref "PCIE-SOUTH") (pin "B8") (pinfunction "IO4_B8") (pintype "passive"))
    )
    (net (code "32") (name "B14_L18_N") (class "Default")
      (node (ref "JM2") (pin "85") (pinfunction "85_85") (pintype "bidirectional"))
      (node (ref "PCIE-SOUTH") (pin "B11") (pinfunction "IO7_B11") (pintype "passive"))
    )
    (net (code "33") (name "B14_L18_P") (class "Default")
      (node (ref "JM2") (pin "87") (pinfunction "87_87") (pintype "bidirectional"))
      (node (ref "PCIE-SOUTH") (pin "B10") (pinfunction "IO6_B10") (pintype "passive"))
    )
    (net (code "34") (name "B14_L19_N") (class "Default")
      (node (ref "JM2") (pin "94") (pinfunction "94_94") (pintype "bidirectional"))
    )
    (net (code "35") (name "B14_L19_P") (class "Default")
      (node (ref "JM2") (pin "92") (pinfunction "92_92") (pintype "bidirectional"))
    )
    (net (code "36") (name "B14_L20_N") (class "Default")
      (node (ref "JM2") (pin "95") (pinfunction "95_95") (pintype "bidirectional"))
      (node (ref "PCIE-SOUTH") (pin "B6") (pinfunction "IO2_B6") (pintype "passive"))
    )
    (net (code "37") (name "B14_L20_P") (class "Default")
      (node (ref "JM2") (pin "93") (pinfunction "93_93") (pintype "bidirectional"))
      (node (ref "PCIE-SOUTH") (pin "B7") (pinfunction "IO3_B7") (pintype "passive"))
    )
    (net (code "38") (name "B14_L21_N") (class "Default")
      (node (ref "JM1") (pin "95") (pinfunction "95_95") (pintype "bidirectional"))
      (node (ref "U1") (pin "1") (pinfunction "EN_1") (pintype "input"))
    )
    (net (code "39") (name "B14_L21_P") (class "Default")
      (node (ref "JM1") (pin "93") (pinfunction "93_93") (pintype "bidirectional"))
      (node (ref "U7") (pin "2") (pinfunction "PG_2") (pintype "power_in"))
    )
    (net (code "40") (name "B14_L22_N") (class "Default")
      (node (ref "JM2") (pin "96") (pinfunction "96_96") (pintype "bidirectional"))
    )
    (net (code "41") (name "B14_L22_P") (class "Default")
      (node (ref "JM2") (pin "98") (pinfunction "98_98") (pintype "bidirectional"))
    )
    (net (code "42") (name "B14_L23_N") (class "Default")
      (node (ref "JM1") (pin "89") (pinfunction "89_89") (pintype "bidirectional"))
    )
    (net (code "43") (name "B14_L23_P") (class "Default")
      (node (ref "JM1") (pin "91") (pinfunction "91_91") (pintype "bidirectional"))
      (node (ref "U6") (pin "2") (pinfunction "PG_2") (pintype "power_in"))
    )
    (net (code "44") (name "B14_L24_N") (class "Default")
      (node (ref "JM1") (pin "85") (pinfunction "85_85") (pintype "bidirectional"))
    )
    (net (code "45") (name "B14_L24_P") (class "Default")
      (node (ref "JM1") (pin "87") (pinfunction "87_87") (pintype "bidirectional"))
    )
    (net (code "46") (name "B14_L25") (class "Default")
      (node (ref "JM2") (pin "97") (pinfunction "97_97") (pintype "bidirectional"))
      (node (ref "PCIE-SOUTH") (pin "B5") (pinfunction "IO1_B5") (pintype "passive"))
    )
    (net (code "47") (name "B15_L1_N") (class "Default")
      (node (ref "JM2") (pin "14") (pinfunction "14_14") (pintype "bidirectional"))
      (node (ref "PCIE-NORTH") (pin "A14") (pinfunction "LVDS_3B_A14") (pintype "passive"))
    )
    (net (code "48") (name "B15_L1_P") (class "Default")
      (node (ref "JM2") (pin "16") (pinfunction "16_16") (pintype "bidirectional"))
      (node (ref "PCIE-NORTH") (pin "A13") (pinfunction "LVDS_3A_A13") (pintype "passive"))
    )
    (net (code "49") (name "B15_L2_N") (class "Default")
      (node (ref "JM2") (pin "20") (pinfunction "20_20") (pintype "bidirectional"))
    )
    (net (code "50") (name "B15_L2_P") (class "Default")
      (node (ref "JM2") (pin "22") (pinfunction "22_22") (pintype "bidirectional"))
    )
    (net (code "51") (name "B15_L3_N") (class "Default")
      (node (ref "JM2") (pin "4") (pinfunction "4_4") (pintype "bidirectional"))
    )
    (net (code "52") (name "B15_L3_P") (class "Default")
      (node (ref "JM2") (pin "2") (pinfunction "2_2") (pintype "bidirectional"))
    )
    (net (code "53") (name "B15_L4_N") (class "Default")
      (node (ref "JM2") (pin "10") (pinfunction "10_10") (pintype "bidirectional"))
    )
    (net (code "54") (name "B15_L4_P") (class "Default")
      (node (ref "JM2") (pin "12") (pinfunction "12_12") (pintype "bidirectional"))
    )
    (net (code "55") (name "B15_L5_N") (class "Default")
      (node (ref "JM2") (pin "8") (pinfunction "8_8") (pintype "bidirectional"))
      (node (ref "PCIE-NORTH") (pin "A16") (pinfunction "LVDS_4A_A16") (pintype "passive"))
    )
    (net (code "56") (name "B15_L5_P") (class "Default")
      (node (ref "JM2") (pin "6") (pinfunction "6_6") (pintype "bidirectional"))
      (node (ref "PCIE-NORTH") (pin "A17") (pinfunction "LVDS_4B_A17") (pintype "passive"))
    )
    (net (code "57") (name "B15_L6_N") (class "Default")
      (node (ref "JM2") (pin "26") (pinfunction "26_26") (pintype "bidirectional"))
      (node (ref "PCIE-NORTH") (pin "A5") (pinfunction "LVDS_1A_A5") (pintype "passive"))
    )
    (net (code "58") (name "B15_L6_P") (class "Default")
      (node (ref "JM2") (pin "24") (pinfunction "24_24") (pintype "bidirectional"))
      (node (ref "PCIE-NORTH") (pin "A6") (pinfunction "LVDS_1B_A6") (pintype "passive"))
    )
    (net (code "59") (name "B15_L7_N") (class "Default")
      (node (ref "JM2") (pin "1") (pinfunction "1_1") (pintype "bidirectional"))
      (node (ref "PCIE-NORTH") (pin "B17") (pinfunction "LVDS_5B_B17") (pintype "passive"))
    )
    (net (code "60") (name "B15_L7_P") (class "Default")
      (node (ref "JM2") (pin "3") (pinfunction "3_3") (pintype "bidirectional"))
      (node (ref "PCIE-NORTH") (pin "B16") (pinfunction "LVDS_5A_B16") (pintype "passive"))
    )
    (net (code "61") (name "B15_L8_N") (class "Default")
      (node (ref "JM2") (pin "7") (pinfunction "7_7") (pintype "bidirectional"))
    )
    (net (code "62") (name "B15_L8_P") (class "Default")
      (node (ref "JM2") (pin "5") (pinfunction "5_5") (pintype "bidirectional"))
    )
    (net (code "63") (name "B15_L9_N") (class "Default")
      (node (ref "JM2") (pin "15") (pinfunction "15_15") (pintype "bidirectional"))
    )
    (net (code "64") (name "B15_L9_P") (class "Default")
      (node (ref "JM2") (pin "13") (pinfunction "13_13") (pintype "bidirectional"))
    )
    (net (code "65") (name "B15_L10_N") (class "Default")
      (node (ref "JM2") (pin "11") (pinfunction "11_11") (pintype "bidirectional"))
      (node (ref "PCIE-NORTH") (pin "A8") (pinfunction "LVDS_2A_A8") (pintype "passive"))
    )
    (net (code "66") (name "B15_L10_P") (class "Default")
      (node (ref "JM2") (pin "9") (pinfunction "9_9") (pintype "bidirectional"))
      (node (ref "PCIE-NORTH") (pin "A9") (pinfunction "LVDS_2B_A9") (pintype "passive"))
    )
    (net (code "67") (name "B15_L11_N") (class "Default")
      (node (ref "JM2") (pin "30") (pinfunction "30_30") (pintype "bidirectional"))
    )
    (net (code "68") (name "B15_L11_P") (class "Default")
      (node (ref "JM2") (pin "28") (pinfunction "28_28") (pintype "bidirectional"))
    )
    (net (code "69") (name "B15_L12_N") (class "Default")
      (node (ref "JM2") (pin "34") (pinfunction "34_34") (pintype "bidirectional"))
      (node (ref "PCIE-SOUTH") (pin "A8") (pinfunction "LVDS_2A_A8") (pintype "passive"))
    )
    (net (code "70") (name "B15_L12_P") (class "Default")
      (node (ref "JM2") (pin "32") (pinfunction "32_32") (pintype "bidirectional"))
      (node (ref "PCIE-SOUTH") (pin "A9") (pinfunction "LVDS_2B_A9") (pintype "passive"))
    )
    (net (code "71") (name "B15_L13_N") (class "Default")
      (node (ref "JM2") (pin "38") (pinfunction "38_38") (pintype "bidirectional"))
      (node (ref "PCIE-SOUTH") (pin "A6") (pinfunction "LVDS_1B_A6") (pintype "passive"))
    )
    (net (code "72") (name "B15_L13_P") (class "Default")
      (node (ref "JM2") (pin "40") (pinfunction "40_40") (pintype "bidirectional"))
      (node (ref "PCIE-SOUTH") (pin "A5") (pinfunction "LVDS_1A_A5") (pintype "passive"))
    )
    (net (code "73") (name "B15_L14_N") (class "Default")
      (node (ref "JM2") (pin "42") (pinfunction "42_42") (pintype "bidirectional"))
    )
    (net (code "74") (name "B15_L14_P") (class "Default")
      (node (ref "JM2") (pin "44") (pinfunction "44_44") (pintype "bidirectional"))
    )
    (net (code "75") (name "B15_L15_N") (class "Default")
      (node (ref "JM2") (pin "19") (pinfunction "19_19") (pintype "bidirectional"))
      (node (ref "PCIE-NORTH") (pin "A3") (pinfunction "LVDS_0B_A3") (pintype "passive"))
    )
    (net (code "76") (name "B15_L15_P") (class "Default")
      (node (ref "JM2") (pin "21") (pinfunction "21_21") (pintype "bidirectional"))
      (node (ref "PCIE-NORTH") (pin "A2") (pinfunction "LVDS_0A_A2") (pintype "passive"))
    )
    (net (code "77") (name "B15_L16_N") (class "Default")
      (node (ref "JM2") (pin "23") (pinfunction "23_23") (pintype "bidirectional"))
    )
    (net (code "78") (name "B15_L16_P") (class "Default")
      (node (ref "JM2") (pin "25") (pinfunction "25_25") (pintype "bidirectional"))
    )
    (net (code "79") (name "B15_L17_N") (class "Default")
      (node (ref "JM2") (pin "31") (pinfunction "31_31") (pintype "bidirectional"))
    )
    (net (code "80") (name "B15_L17_P") (class "Default")
      (node (ref "JM2") (pin "33") (pinfunction "33_33") (pintype "bidirectional"))
    )
    (net (code "81") (name "B15_L18_N") (class "Default")
      (node (ref "JM2") (pin "27") (pinfunction "27_27") (pintype "bidirectional"))
      (node (ref "PCIE-SOUTH") (pin "A17") (pinfunction "LVDS_4B_A17") (pintype "passive"))
    )
    (net (code "82") (name "B15_L18_P") (class "Default")
      (node (ref "JM2") (pin "29") (pinfunction "29_29") (pintype "bidirectional"))
      (node (ref "PCIE-SOUTH") (pin "A16") (pinfunction "LVDS_4A_A16") (pintype "passive"))
    )
    (net (code "83") (name "B15_L19_N") (class "Default")
      (node (ref "JM2") (pin "41") (pinfunction "41_41") (pintype "bidirectional"))
      (node (ref "PCIE-SOUTH") (pin "B17") (pinfunction "LVDS_5B_B17") (pintype "passive"))
    )
    (net (code "84") (name "B15_L19_P") (class "Default")
      (node (ref "JM2") (pin "43") (pinfunction "43_43") (pintype "bidirectional"))
      (node (ref "PCIE-SOUTH") (pin "B16") (pinfunction "LVDS_5A_B16") (pintype "passive"))
    )
    (net (code "85") (name "B15_L20_N") (class "Default")
      (node (ref "JM2") (pin "50") (pinfunction "50_50") (pintype "bidirectional"))
    )
    (net (code "86") (name "B15_L20_P") (class "Default")
      (node (ref "JM2") (pin "52") (pinfunction "52_52") (pintype "bidirectional"))
    )
    (net (code "87") (name "B15_L21_N") (class "Default")
      (node (ref "JM2") (pin "45") (pinfunction "45_45") (pintype "bidirectional"))
    )
    (net (code "88") (name "B15_L21_P") (class "Default")
      (node (ref "JM2") (pin "47") (pinfunction "47_47") (pintype "bidirectional"))
    )
    (net (code "89") (name "B15_L22_N") (class "Default")
      (node (ref "JM2") (pin "46") (pinfunction "46_46") (pintype "bidirectional"))
      (node (ref "PCIE-SOUTH") (pin "A3") (pinfunction "LVDS_0B_A3") (pintype "passive"))
    )
    (net (code "90") (name "B15_L22_P") (class "Default")
      (node (ref "JM2") (pin "48") (pinfunction "48_48") (pintype "bidirectional"))
      (node (ref "PCIE-SOUTH") (pin "A2") (pinfunction "LVDS_0A_A2") (pintype "passive"))
    )
    (net (code "91") (name "B15_L23_N") (class "Default")
      (node (ref "JM2") (pin "51") (pinfunction "51_51") (pintype "bidirectional"))
      (node (ref "PCIE-SOUTH") (pin "A13") (pinfunction "LVDS_3A_A13") (pintype "passive"))
    )
    (net (code "92") (name "B15_L23_P") (class "Default")
      (node (ref "JM2") (pin "49") (pinfunction "49_49") (pintype "bidirectional"))
      (node (ref "PCIE-SOUTH") (pin "A14") (pinfunction "LVDS_3B_A14") (pintype "passive"))
    )
    (net (code "93") (name "B15_L24_N") (class "Default")
      (node (ref "JM2") (pin "37") (pinfunction "37_37") (pintype "bidirectional"))
    )
    (net (code "94") (name "B15_L24_P") (class "Default")
      (node (ref "JM2") (pin "39") (pinfunction "39_39") (pintype "bidirectional"))
    )
    (net (code "95") (name "B34_L1_N") (class "Default")
      (node (ref "JM1") (pin "37") (pinfunction "37_37") (pintype "bidirectional"))
    )
    (net (code "96") (name "B34_L1_P") (class "Default")
      (node (ref "JM1") (pin "35") (pinfunction "35_35") (pintype "bidirectional"))
    )
    (net (code "97") (name "B34_L2_N") (class "Default")
      (node (ref "JM1") (pin "33") (pinfunction "33_33") (pintype "bidirectional"))
    )
    (net (code "98") (name "B34_L2_P") (class "Default")
      (node (ref "JM1") (pin "31") (pinfunction "31_31") (pintype "bidirectional"))
    )
    (net (code "99") (name "B34_L3_N") (class "Default")
      (node (ref "JM1") (pin "42") (pinfunction "42_42") (pintype "bidirectional"))
      (node (ref "U4") (pin "13") (pinfunction "SCLK_13") (pintype "input"))
    )
    (net (code "100") (name "B34_L3_P") (class "Default")
      (node (ref "JM1") (pin "40") (pinfunction "40_40") (pintype "bidirectional"))
      (node (ref "U4") (pin "17") (pinfunction "GPIO0_17") (pintype "bidirectional"))
    )
    (net (code "101") (name "B34_L4_N") (class "Default")
      (node (ref "JM1") (pin "41") (pinfunction "41_41") (pintype "bidirectional"))
      (node (ref "U4") (pin "12") (pinfunction "SDOUT_12") (pintype "output"))
    )
    (net (code "102") (name "B34_L4_P") (class "Default")
      (node (ref "JM1") (pin "39") (pinfunction "39_39") (pintype "bidirectional"))
    )
    (net (code "103") (name "B34_L5_N") (class "Default")
      (node (ref "JM1") (pin "45") (pinfunction "45_45") (pintype "bidirectional"))
      (node (ref "U4") (pin "10") (pinfunction "~{CS}_10") (pintype "input"))
    )
    (net (code "104") (name "B34_L5_P") (class "Default")
      (node (ref "JM1") (pin "43") (pinfunction "43_43") (pintype "bidirectional"))
      (node (ref "U4") (pin "11") (pinfunction "SDIN_11") (pintype "input"))
    )
    (net (code "105") (name "B34_L6_N") (class "Default")
      (node (ref "JM1") (pin "34") (pinfunction "34_34") (pintype "bidirectional"))
    )
    (net (code "106") (name "B34_L6_P") (class "Default")
      (node (ref "JM1") (pin "32") (pinfunction "32_32") (pintype "bidirectional"))
    )
    (net (code "107") (name "B34_L7_N") (class "Default")
      (node (ref "JM1") (pin "38") (pinfunction "38_38") (pintype "bidirectional"))
      (node (ref "U4") (pin "18") (pinfunction "GPIO1_18") (pintype "bidirectional"))
    )
    (net (code "108") (name "B34_L7_P") (class "Default")
      (node (ref "JM1") (pin "36") (pinfunction "36_36") (pintype "bidirectional"))
    )
    (net (code "109") (name "B34_L8_N") (class "Default")
      (node (ref "JM1") (pin "52") (pinfunction "52_52") (pintype "bidirectional"))
      (node (ref "U3") (pin "13") (pinfunction "SCLK_13") (pintype "input"))
    )
    (net (code "110") (name "B34_L8_P") (class "Default")
      (node (ref "JM1") (pin "50") (pinfunction "50_50") (pintype "bidirectional"))
      (node (ref "U3") (pin "12") (pinfunction "SDOUT_12") (pintype "output"))
    )
    (net (code "111") (name "B34_L9_N") (class "Default")
      (node (ref "JM1") (pin "46") (pinfunction "46_46") (pintype "bidirectional"))
      (node (ref "U4") (pin "33") (pinfunction "GPIO2_33") (pintype "bidirectional"))
    )
    (net (code "112") (name "B34_L9_P") (class "Default")
      (node (ref "JM1") (pin "44") (pinfunction "44_44") (pintype "bidirectional"))
      (node (ref "U4") (pin "36") (pinfunction "GPIO3_36") (pintype "bidirectional"))
    )
    (net (code "113") (name "B34_L10_N") (class "Default")
      (node (ref "JM1") (pin "51") (pinfunction "51_51") (pintype "bidirectional"))
      (node (ref "U5") (pin "11") (pinfunction "SDIN_11") (pintype "input"))
    )
    (net (code "114") (name "B34_L10_P") (class "Default")
      (node (ref "JM1") (pin "49") (pinfunction "49_49") (pintype "bidirectional"))
      (node (ref "U5") (pin "10") (pinfunction "~{CS}_10") (pintype "input"))
    )
    (net (code "115") (name "B34_L11_N") (class "Default")
      (node (ref "JM1") (pin "53") (pinfunction "53_53") (pintype "bidirectional"))
      (node (ref "U5") (pin "12") (pinfunction "SDOUT_12") (pintype "output"))
    )
    (net (code "116") (name "B34_L11_P") (class "Default")
      (node (ref "JM1") (pin "55") (pinfunction "55_55") (pintype "bidirectional"))
      (node (ref "U5") (pin "17") (pinfunction "GPIO0_17") (pintype "bidirectional"))
    )
    (net (code "117") (name "B34_L12_N") (class "Default")
      (node (ref "JM1") (pin "57") (pinfunction "57_57") (pintype "bidirectional"))
      (node (ref "U5") (pin "18") (pinfunction "GPIO1_18") (pintype "bidirectional"))
    )
    (net (code "118") (name "B34_L12_P") (class "Default")
      (node (ref "JM1") (pin "59") (pinfunction "59_59") (pintype "bidirectional"))
      (node (ref "U3") (pin "11") (pinfunction "SDIN_11") (pintype "input"))
    )
    (net (code "119") (name "B34_L13_N") (class "Default")
      (node (ref "JM1") (pin "56") (pinfunction "56_56") (pintype "bidirectional"))
      (node (ref "U3") (pin "18") (pinfunction "GPIO1_18") (pintype "bidirectional"))
    )
    (net (code "120") (name "B34_L13_P") (class "Default")
      (node (ref "JM1") (pin "54") (pinfunction "54_54") (pintype "bidirectional"))
      (node (ref "U3") (pin "17") (pinfunction "GPIO0_17") (pintype "bidirectional"))
    )
    (net (code "121") (name "B34_L14_N") (class "Default")
      (node (ref "JM1") (pin "60") (pinfunction "60_60") (pintype "bidirectional"))
      (node (ref "U3") (pin "36") (pinfunction "GPIO3_36") (pintype "bidirectional"))
    )
    (net (code "122") (name "B34_L14_P") (class "Default")
      (node (ref "JM1") (pin "58") (pinfunction "58_58") (pintype "bidirectional"))
      (node (ref "U3") (pin "33") (pinfunction "GPIO2_33") (pintype "bidirectional"))
    )
    (net (code "123") (name "B34_L15_N") (class "Default")
      (node (ref "JM1") (pin "62") (pinfunction "62_62") (pintype "bidirectional"))
    )
    (net (code "124") (name "B34_L15_P") (class "Default")
      (node (ref "JM1") (pin "64") (pinfunction "64_64") (pintype "bidirectional"))
    )
    (net (code "125") (name "B34_L16_N") (class "Default")
      (node (ref "JM1") (pin "68") (pinfunction "68_68") (pintype "bidirectional"))
    )
    (net (code "126") (name "B34_L16_P") (class "Default")
      (node (ref "JM1") (pin "70") (pinfunction "70_70") (pintype "bidirectional"))
      (node (ref "U4") (pin "32") (pinfunction "RCLK_32") (pintype "input"))
    )
    (net (code "127") (name "B34_L17_N") (class "Default")
      (node (ref "JM1") (pin "63") (pinfunction "63_63") (pintype "bidirectional"))
      (node (ref "U3") (pin "10") (pinfunction "~{CS}_10") (pintype "input"))
    )
    (net (code "128") (name "B34_L17_P") (class "Default")
      (node (ref "JM1") (pin "65") (pinfunction "65_65") (pintype "bidirectional"))
      (node (ref "U5") (pin "36") (pinfunction "GPIO3_36") (pintype "bidirectional"))
    )
    (net (code "129") (name "B34_L18_N") (class "Default")
      (node (ref "JM1") (pin "74") (pinfunction "74_74") (pintype "bidirectional"))
    )
    (net (code "130") (name "B34_L18_P") (class "Default")
      (node (ref "JM1") (pin "72") (pinfunction "72_72") (pintype "bidirectional"))
    )
    (net (code "131") (name "B34_L19_N") (class "Default")
      (node (ref "JM1") (pin "71") (pinfunction "71_71") (pintype "bidirectional"))
    )
    (net (code "132") (name "B34_L19_P") (class "Default")
      (node (ref "JM1") (pin "73") (pinfunction "73_73") (pintype "bidirectional"))
      (node (ref "U5") (pin "32") (pinfunction "RCLK_32") (pintype "input"))
    )
    (net (code "133") (name "B34_L20_N") (class "Default")
      (node (ref "JM1") (pin "76") (pinfunction "76_76") (pintype "bidirectional"))
      (node (ref "R6") (pin "1") (pinfunction "1_1") (pintype "passive"))
    )
    (net (code "134") (name "B34_L20_P") (class "Default")
      (node (ref "JM1") (pin "78") (pinfunction "78_78") (pintype "bidirectional"))
      (node (ref "R7") (pin "1") (pinfunction "1_1") (pintype "passive"))
    )
    (net (code "135") (name "B34_L21_N") (class "Default")
      (node (ref "JM1") (pin "69") (pinfunction "69_69") (pintype "bidirectional"))
    )
    (net (code "136") (name "B34_L21_P") (class "Default")
      (node (ref "JM1") (pin "67") (pinfunction "67_67") (pintype "bidirectional"))
      (node (ref "U5") (pin "33") (pinfunction "GPIO2_33") (pintype "bidirectional"))
    )
    (net (code "137") (name "B34_L22_N") (class "Default")
      (node (ref "JM1") (pin "75") (pinfunction "75_75") (pintype "bidirectional"))
    )
    (net (code "138") (name "B34_L22_P") (class "Default")
      (node (ref "JM1") (pin "77") (pinfunction "77_77") (pintype "bidirectional"))
    )
    (net (code "139") (name "B34_L23_N") (class "Default")
      (node (ref "JM1") (pin "79") (pinfunction "79_79") (pintype "bidirectional"))
    )
    (net (code "140") (name "B34_L23_P") (class "Default")
      (node (ref "JM1") (pin "81") (pinfunction "81_81") (pintype "bidirectional"))
    )
    (net (code "141") (name "B34_L24_N") (class "Default")
      (node (ref "JM1") (pin "80") (pinfunction "80_80") (pintype "bidirectional"))
      (node (ref "R8") (pin "1") (pinfunction "1_1") (pintype "passive"))
    )
    (net (code "142") (name "B34_L24_P") (class "Default")
      (node (ref "JM1") (pin "82") (pinfunction "82_82") (pintype "bidirectional"))
      (node (ref "R9") (pin "1") (pinfunction "1_1") (pintype "passive"))
    )
    (net (code "143") (name "BOOTMODE") (class "Default")
      (node (ref "JM2") (pin "100") (pinfunction "100_100") (pintype "bidirectional"))
    )
    (net (code "144") (name "DONE") (class "Default")
      (node (ref "D5") (pin "A") (pinfunction "A_A") (pintype "passive"))
      (node (ref "JM1") (pin "96") (pinfunction "96_96") (pintype "bidirectional"))
      (node (ref "R4") (pin "1") (pinfunction "1_1") (pintype "passive"))
    )
    (net (code "145") (name "EN_A") (class "Default")
      (node (ref "R99") (pin "1") (pinfunction "1_1") (pintype "passive"))
      (node (ref "U6") (pin "1") (pinfunction "EN_1") (pintype "input"))
    )
    (net (code "146") (name "EN_B") (class "Default")
      (node (ref "R21") (pin "1") (pinfunction "1_1") (pintype "passive"))
      (node (ref "U7") (pin "1") (pinfunction "EN_1") (pintype "input"))
    )
    (net (code "147") (name "GND") (class "Default")
      (node (ref "C1") (pin "2") (pinfunction "2_2") (pintype "passive"))
      (node (ref "C10") (pin "2") (pinfunction "2_2") (pintype "passive"))
      (node (ref "C11") (pin "2") (pinfunction "2_2") (pintype "passive"))
      (node (ref "C12") (pin "2") (pinfunction "2_2") (pintype "passive"))
      (node (ref "C13") (pin "2") (pinfunction "2_2") (pintype "passive"))
      (node (ref "C14") (pin "2") (pinfunction "2_2") (pintype "passive"))
      (node (ref "C15") (pin "2") (pinfunction "2_2") (pintype "passive"))
      (node (ref "C16") (pin "2") (pinfunction "2_2") (pintype "passive"))
      (node (ref "C17") (pin "2") (pinfunction "2_2") (pintype "passive"))
      (node (ref "C18") (pin "2") (pinfunction "2_2") (pintype "passive"))
      (node (ref "C19") (pin "2") (pinfunction "2_2") (pintype "passive"))
      (node (ref "C25") (pin "2") (pinfunction "2_2") (pintype "passive"))
      (node (ref "C26") (pin "2") (pinfunction "2_2") (pintype "passive"))
      (node (ref "C27") (pin "2") (pinfunction "2_2") (pintype "passive"))
      (node (ref "C28") (pin "2") (pinfunction "2_2") (pintype "passive"))
      (node (ref "C29") (pin "2") (pinfunction "2_2") (pintype "passive"))
      (node (ref "C30") (pin "2") (pinfunction "2_2") (pintype "passive"))
      (node (ref "C31") (pin "2") (pinfunction "2_2") (pintype "passive"))
      (node (ref "C32") (pin "2") (pinfunction "2_2") (pintype "passive"))
      (node (ref "C33") (pin "2") (pinfunction "2_2") (pintype "passive"))
      (node (ref "C34") (pin "2") (pinfunction "2_2") (pintype "passive"))
      (node (ref "C35") (pin "2") (pinfunction "2_2") (pintype "passive"))
      (node (ref "C36") (pin "2") (pinfunction "2_2") (pintype "passive"))
      (node (ref "C37") (pin "2") (pinfunction "2_2") (pintype "passive"))
      (node (ref "C4") (pin "2") (pinfunction "2_2") (pintype "passive"))
      (node (ref "C43") (pin "2") (pinfunction "2_2") (pintype "passive"))
      (node (ref "C44") (pin "2") (pinfunction "2_2") (pintype "passive"))
      (node (ref "C45") (pin "2") (pinfunction "2_2") (pintype "passive"))
      (node (ref "C46") (pin "2") (pinfunction "2_2") (pintype "passive"))
      (node (ref "C47") (pin "2") (pinfunction "2_2") (pintype "passive"))
      (node (ref "C48") (pin "2") (pinfunction "2_2") (pintype "passive"))
      (node (ref "C49") (pin "2") (pinfunction "2_2") (pintype "passive"))
      (node (ref "C50") (pin "2") (pinfunction "2_2") (pintype "passive"))
      (node (ref "C51") (pin "2") (pinfunction "2_2") (pintype "passive"))
      (node (ref "C52") (pin "2") (pinfunction "2_2") (pintype "passive"))
      (node (ref "C53") (pin "2") (pinfunction "2_2") (pintype "passive"))
      (node (ref "C54") (pin "2") (pinfunction "2_2") (pintype "passive"))
      (node (ref "C55") (pin "2") (pinfunction "2_2") (pintype "passive"))
      (node (ref "C56") (pin "2") (pinfunction "2_2") (pintype "passive"))
      (node (ref "C57") (pin "2") (pinfunction "2_2") (pintype "passive"))
      (node (ref "C58") (pin "2") (pinfunction "2_2") (pintype "passive"))
      (node (ref "C59") (pin "2") (pinfunction "2_2") (pintype "passive"))
      (node (ref "C8") (pin "2") (pinfunction "2_2") (pintype "passive"))
      (node (ref "C9") (pin "2") (pinfunction "2_2") (pintype "passive"))
      (node (ref "D5") (pin "C") (pinfunction "C_C") (pintype "passive"))
      (node (ref "JM1") (pin "100") (pinfunction "100_100") (pintype "bidirectional"))
      (node (ref "JM1") (pin "11") (pinfunction "11_11") (pintype "bidirectional"))
      (node (ref "JM1") (pin "12") (pinfunction "12_12") (pintype "bidirectional"))
      (node (ref "JM1") (pin "17") (pinfunction "17_17") (pintype "bidirectional"))
      (node (ref "JM1") (pin "18") (pinfunction "18_18") (pintype "bidirectional"))
      (node (ref "JM1") (pin "23") (pinfunction "23_23") (pintype "bidirectional"))
      (node (ref "JM1") (pin "24") (pinfunction "24_24") (pintype "bidirectional"))
      (node (ref "JM1") (pin "29") (pinfunction "29_29") (pintype "bidirectional"))
      (node (ref "JM1") (pin "30") (pinfunction "30_30") (pintype "bidirectional"))
      (node (ref "JM1") (pin "47") (pinfunction "47_47") (pintype "bidirectional"))
      (node (ref "JM1") (pin "48") (pinfunction "48_48") (pintype "bidirectional"))
      (node (ref "JM1") (pin "5") (pinfunction "5_5") (pintype "bidirectional"))
      (node (ref "JM1") (pin "6") (pinfunction "6_6") (pintype "bidirectional"))
      (node (ref "JM1") (pin "66") (pinfunction "66_66") (pintype "bidirectional"))
      (node (ref "JM1") (pin "84") (pinfunction "84_84") (pintype "bidirectional"))
      (node (ref "JM1") (pin "98") (pinfunction "98_98") (pintype "bidirectional"))
      (node (ref "JM1") (pin "F1") (pinfunction "F1_F1") (pintype "bidirectional"))
      (node (ref "JM1") (pin "F2") (pinfunction "F2_F2") (pintype "bidirectional"))
      (node (ref "JM2") (pin "17") (pinfunction "17_17") (pintype "bidirectional"))
      (node (ref "JM2") (pin "35") (pinfunction "35_35") (pintype "bidirectional"))
      (node (ref "JM2") (pin "36") (pinfunction "36_36") (pintype "bidirectional"))
      (node (ref "JM2") (pin "72") (pinfunction "72_72") (pintype "bidirectional"))
      (node (ref "JM2") (pin "83") (pinfunction "83_83") (pintype "bidirectional"))
      (node (ref "JM2") (pin "90") (pinfunction "90_90") (pintype "bidirectional"))
      (node (ref "JM2") (pin "F1") (pinfunction "F1_F1") (pintype "bidirectional"))
      (node (ref "JM2") (pin "F2") (pinfunction "F2_F2") (pintype "bidirectional"))
      (node (ref "JP2") (pin "3") (pinfunction "3_3") (pintype "passive"))
      (node (ref "JTAG") (pin "1") (pinfunction "1_1") (pintype "passive"))
      (node (ref "JTAG") (pin "11") (pinfunction "11_11") (pintype "passive"))
      (node (ref "JTAG") (pin "13") (pinfunction "13_13") (pintype "passive"))
      (node (ref "JTAG") (pin "3") (pinfunction "3_3") (pintype "passive"))
      (node (ref "JTAG") (pin "5") (pinfunction "5_5") (pintype "passive"))
      (node (ref "JTAG") (pin "7") (pinfunction "7_7") (pintype "passive"))
      (node (ref "JTAG") (pin "9") (pinfunction "9_9") (pintype "passive"))
      (node (ref "OUT1") (pin "2@1") (pinfunction "GND_2@1") (pintype "passive"))
      (node (ref "OUT1") (pin "2@2") (pinfunction "GND_2@2") (pintype "passive"))
      (node (ref "OUT1") (pin "2@3") (pinfunction "GND_2@3") (pintype "passive"))
      (node (ref "OUT2") (pin "2@1") (pinfunction "GND_2@1") (pintype "passive"))
      (node (ref "OUT2") (pin "2@2") (pinfunction "GND_2@2") (pintype "passive"))
      (node (ref "OUT2") (pin "2@3") (pinfunction "GND_2@3") (pintype "passive"))
      (node (ref "PCIE-NORTH") (pin "A1") (pinfunction "GND_A1") (pintype "passive"))
      (node (ref "PCIE-NORTH") (pin "A10") (pinfunction "GND_A10") (pintype "passive"))
      (node (ref "PCIE-NORTH") (pin "A12") (pinfunction "GND_A12") (pintype "passive"))
      (node (ref "PCIE-NORTH") (pin "A15") (pinfunction "GND_A15") (pintype "passive"))
      (node (ref "PCIE-NORTH") (pin "A18") (pinfunction "GND_A18") (pintype "passive"))
      (node (ref "PCIE-NORTH") (pin "A4") (pinfunction "GND_A4") (pintype "passive"))
      (node (ref "PCIE-NORTH") (pin "A7") (pinfunction "GND_A7") (pintype "passive"))
      (node (ref "PCIE-NORTH") (pin "B15") (pinfunction "GND_B15") (pintype "passive"))
      (node (ref "PCIE-NORTH") (pin "B18") (pinfunction "GND_B18") (pintype "passive"))
      (node (ref "PCIE-SOUTH") (pin "A1") (pinfunction "GND_A1") (pintype "passive"))
      (node (ref "PCIE-SOUTH") (pin "A10") (pinfunction "GND_A10") (pintype "passive"))
      (node (ref "PCIE-SOUTH") (pin "A12") (pinfunction "GND_A12") (pintype "passive"))
      (node (ref "PCIE-SOUTH") (pin "A15") (pinfunction "GND_A15") (pintype "passive"))
      (node (ref "PCIE-SOUTH") (pin "A18") (pinfunction "GND_A18") (pintype "passive"))
      (node (ref "PCIE-SOUTH") (pin "A4") (pinfunction "GND_A4") (pintype "passive"))
      (node (ref "PCIE-SOUTH") (pin "A7") (pinfunction "GND_A7") (pintype "passive"))
      (node (ref "PCIE-SOUTH") (pin "B15") (pinfunction "GND_B15") (pintype "passive"))
      (node (ref "PCIE-SOUTH") (pin "B18") (pinfunction "GND_B18") (pintype "passive"))
      (node (ref "R10") (pin "2") (pinfunction "2_2") (pintype "passive"))
      (node (ref "R11") (pin "2") (pinfunction "2_2") (pintype "passive"))
      (node (ref "R12") (pin "2") (pinfunction "2_2") (pintype "passive"))
      (node (ref "R13") (pin "2") (pinfunction "2_2") (pintype "passive"))
      (node (ref "R14") (pin "2") (pinfunction "2_2") (pintype "passive"))
      (node (ref "R15") (pin "2") (pinfunction "2_2") (pintype "passive"))
      (node (ref "R16") (pin "2") (pinfunction "2_2") (pintype "passive"))
      (node (ref "R18") (pin "1") (pinfunction "1_1") (pintype "passive"))
      (node (ref "R20") (pin "1") (pinfunction "1_1") (pintype "passive"))
      (node (ref "R3") (pin "2") (pinfunction "2_2") (pintype "passive"))
      (node (ref "SDI-IN") (pin "2@1") (pinfunction "GND_2@1") (pintype "passive"))
      (node (ref "SDI-IN") (pin "2@2") (pinfunction "GND_2@2") (pintype "passive"))
      (node (ref "SDI-IN") (pin "2@3") (pinfunction "GND_2@3") (pintype "passive"))
      (node (ref "U1") (pin "3") (pinfunction "GND_3") (pintype "passive"))
      (node (ref "U2") (pin "1") (pinfunction "A0_1") (pintype "input"))
      (node (ref "U2") (pin "2") (pinfunction "A1_2") (pintype "input"))
      (node (ref "U2") (pin "3") (pinfunction "A2_3") (pintype "input"))
      (node (ref "U2") (pin "4") (pinfunction "GND_4") (pintype "passive"))
      (node (ref "U2") (pin "EP") (pinfunction "EP_EP") (pintype "passive"))
      (node (ref "U3") (pin "1") (pinfunction "VEE_SDI_1") (pintype "power_in"))
      (node (ref "U3") (pin "14") (pinfunction "VSS_14") (pintype "power_in"))
      (node (ref "U3") (pin "15") (pinfunction "VSS_15") (pintype "power_in"))
      (node (ref "U3") (pin "19") (pinfunction "VEE_CORE_19") (pintype "power_in"))
      (node (ref "U3") (pin "21") (pinfunction "VEEO_21") (pintype "power_in"))
      (node (ref "U3") (pin "28") (pinfunction "VEEO_28") (pintype "power_in"))
      (node (ref "U3") (pin "31") (pinfunction "VEE_CORE_31") (pintype "power_in"))
      (node (ref "U3") (pin "37") (pinfunction "VEE_CORE_37") (pintype "power_in"))
      (node (ref "U3") (pin "38") (pinfunction "VEE_CORE_38") (pintype "power_in"))
      (node (ref "U3") (pin "8") (pinfunction "VEE_SDI_8") (pintype "power_in"))
      (node (ref "U4") (pin "1") (pinfunction "VEE_DDI_1") (pintype "power_in"))
      (node (ref "U4") (pin "14") (pinfunction "VSS_14") (pintype "power_in"))
      (node (ref "U4") (pin "15") (pinfunction "VSS_15") (pintype "power_in"))
      (node (ref "U4") (pin "19") (pinfunction "VEE_CORE_19") (pintype "power_in"))
      (node (ref "U4") (pin "21") (pinfunction "VEEO_21") (pintype "power_in"))
      (node (ref "U4") (pin "28") (pinfunction "VEEO_28") (pintype "power_in"))
      (node (ref "U4") (pin "31") (pinfunction "VEE_CORE_31") (pintype "power_in"))
      (node (ref "U4") (pin "37") (pinfunction "VEE_CORE_37") (pintype "power_in"))
      (node (ref "U4") (pin "38") (pinfunction "VEE_CORE_38") (pintype "power_in"))
      (node (ref "U4") (pin "8") (pinfunction "VEE_DDI_8") (pintype "power_in"))
      (node (ref "U5") (pin "1") (pinfunction "VEE_DDI_1") (pintype "power_in"))
      (node (ref "U5") (pin "14") (pinfunction "VSS_14") (pintype "power_in"))
      (node (ref "U5") (pin "15") (pinfunction "VSS_15") (pintype "power_in"))
      (node (ref "U5") (pin "19") (pinfunction "VEE_CORE_19") (pintype "power_in"))
      (node (ref "U5") (pin "21") (pinfunction "VEEO_21") (pintype "power_in"))
      (node (ref "U5") (pin "28") (pinfunction "VEEO_28") (pintype "power_in"))
      (node (ref "U5") (pin "31") (pinfunction "VEE_CORE_31") (pintype "power_in"))
      (node (ref "U5") (pin "37") (pinfunction "VEE_CORE_37") (pintype "power_in"))
      (node (ref "U5") (pin "38") (pinfunction "VEE_CORE_38") (pintype "power_in"))
      (node (ref "U5") (pin "8") (pinfunction "VEE_DDI_8") (pintype "power_in"))
      (node (ref "U6") (pin "5") (pinfunction "GND_5") (pintype "passive"))
      (node (ref "U6") (pin "6") (pinfunction "GND_6") (pintype "passive"))
      (node (ref "U6") (pin "EP") (pinfunction "GND_EP") (pintype "passive"))
      (node (ref "U7") (pin "5") (pinfunction "GND_5") (pintype "passive"))
      (node (ref "U7") (pin "6") (pinfunction "GND_6") (pintype "passive"))
      (node (ref "U7") (pin "EP") (pinfunction "GND_EP") (pintype "passive"))
    )
    (net (code "148") (name "I2C_V") (class "Default")
      (node (ref "C4") (pin "1") (pinfunction "1_1") (pintype "passive"))
      (node (ref "PCIE-NORTH") (pin "B3") (pinfunction "V_I2C_B3") (pintype "passive"))
      (node (ref "R2") (pin "1") (pinfunction "1_1") (pintype "passive"))
      (node (ref "U2") (pin "8") (pinfunction "VCC_8") (pintype "power_in"))
    )
    (net (code "149") (name "MGT_CLK0_N") (class "Default")
      (node (ref "C3") (pin "2") (pinfunction "2_2") (pintype "passive"))
      (node (ref "JM1") (pin "4") (pinfunction "4_4") (pintype "bidirectional"))
    )
    (net (code "150") (name "MGT_CLK0_P") (class "Default")
      (node (ref "C2") (pin "2") (pinfunction "2_2") (pintype "passive"))
      (node (ref "JM1") (pin "2") (pinfunction "2_2") (pintype "bidirectional"))
    )
    (net (code "151") (name "MGT_RX0_N") (class "Default")
      (node (ref "JM1") (pin "21") (pinfunction "21_21") (pintype "bidirectional"))
      (node (ref "U3") (pin "27") (pinfunction "DDO0_27") (pintype "output"))
    )
    (net (code "152") (name "MGT_RX0_P") (class "Default")
      (node (ref "JM1") (pin "19") (pinfunction "19_19") (pintype "bidirectional"))
      (node (ref "U3") (pin "26") (pinfunction "~{DDO0}_26") (pintype "output"))
    )
    (net (code "153") (name "MGT_RX1_N") (class "Default")
      (node (ref "JM1") (pin "15") (pinfunction "15_15") (pintype "bidirectional"))
      (node (ref "U3") (pin "23") (pinfunction "DDO1/RCO_23") (pintype "output"))
    )
    (net (code "154") (name "MGT_RX1_P") (class "Default")
      (node (ref "JM1") (pin "13") (pinfunction "13_13") (pintype "bidirectional"))
      (node (ref "U3") (pin "22") (pinfunction "~{DDO1}/~{RCO}_22") (pintype "output"))
    )
    (net (code "155") (name "MGT_RX2_N") (class "Default")
      (node (ref "JM1") (pin "9") (pinfunction "9_9") (pintype "bidirectional"))
    )
    (net (code "156") (name "MGT_RX2_P") (class "Default")
      (node (ref "JM1") (pin "7") (pinfunction "7_7") (pintype "bidirectional"))
    )
    (net (code "157") (name "MGT_RX3_N") (class "Default")
      (node (ref "JM1") (pin "3") (pinfunction "3_3") (pintype "bidirectional"))
    )
    (net (code "158") (name "MGT_RX3_P") (class "Default")
      (node (ref "JM1") (pin "1") (pinfunction "1_1") (pintype "bidirectional"))
    )
    (net (code "159") (name "MGT_TX0_N") (class "Default")
      (node (ref "JM1") (pin "28") (pinfunction "28_28") (pintype "bidirectional"))
      (node (ref "U5") (pin "6") (pinfunction "DDI_6") (pintype "input"))
    )
    (net (code "160") (name "MGT_TX0_P") (class "Default")
      (node (ref "JM1") (pin "26") (pinfunction "26_26") (pintype "bidirectional"))
      (node (ref "U5") (pin "7") (pinfunction "~{DDI}_7") (pintype "input"))
    )
    (net (code "161") (name "MGT_TX1_N") (class "Default")
      (node (ref "JM1") (pin "22") (pinfunction "22_22") (pintype "bidirectional"))
      (node (ref "U4") (pin "6") (pinfunction "DDI_6") (pintype "input"))
    )
    (net (code "162") (name "MGT_TX1_P") (class "Default")
      (node (ref "JM1") (pin "20") (pinfunction "20_20") (pintype "bidirectional"))
      (node (ref "U4") (pin "7") (pinfunction "~{DDI}_7") (pintype "input"))
    )
    (net (code "163") (name "MGT_TX2_N") (class "Default")
      (node (ref "JM1") (pin "16") (pinfunction "16_16") (pintype "bidirectional"))
    )
    (net (code "164") (name "MGT_TX2_P") (class "Default")
      (node (ref "JM1") (pin "14") (pinfunction "14_14") (pintype "bidirectional"))
    )
    (net (code "165") (name "MGT_TX3_N") (class "Default")
      (node (ref "JM1") (pin "10") (pinfunction "10_10") (pintype "bidirectional"))
    )
    (net (code "166") (name "MGT_TX3_P") (class "Default")
      (node (ref "JM1") (pin "8") (pinfunction "8_8") (pintype "bidirectional"))
    )
    (net (code "167") (name "M_1V8") (class "Default")
      (node (ref "JM2") (pin "18") (pinfunction "18_18") (pintype "bidirectional"))
      (node (ref "R5") (pin "2") (pinfunction "2_2") (pintype "passive"))
    )
    (net (code "168") (name "N$83") (class "Default")
      (node (ref "U5") (pin "13") (pinfunction "SCLK_13") (pintype "input"))
    )
    (net (code "169") (name "N_5V") (class "Default")
      (node (ref "PCIE-NORTH") (pin "B12") (pinfunction "5V_B12") (pintype "passive"))
    )
    (net (code "170") (name "N_IO0") (class "Default")
      (node (ref "PCIE-NORTH") (pin "B4") (pinfunction "IO0_B4") (pintype "passive"))
    )
    (net (code "171") (name "N_IO1") (class "Default")
      (node (ref "PCIE-NORTH") (pin "B5") (pinfunction "IO1_B5") (pintype "passive"))
    )
    (net (code "172") (name "N_IO2") (class "Default")
      (node (ref "PCIE-NORTH") (pin "B6") (pinfunction "IO2_B6") (pintype "passive"))
    )
    (net (code "173") (name "N_IO3") (class "Default")
      (node (ref "PCIE-NORTH") (pin "B7") (pinfunction "IO3_B7") (pintype "passive"))
    )
    (net (code "174") (name "N_IO4") (class "Default")
      (node (ref "PCIE-NORTH") (pin "B8") (pinfunction "IO4_B8") (pintype "passive"))
    )
    (net (code "175") (name "N_IO5") (class "Default")
      (node (ref "PCIE-NORTH") (pin "B9") (pinfunction "IO5_B9") (pintype "passive"))
    )
    (net (code "176") (name "N_IO6") (class "Default")
      (node (ref "PCIE-NORTH") (pin "B10") (pinfunction "IO6_B10") (pintype "passive"))
    )
    (net (code "177") (name "N_IO7") (class "Default")
      (node (ref "PCIE-NORTH") (pin "B11") (pinfunction "IO7_B11") (pintype "passive"))
    )
    (net (code "178") (name "N_PCIE_V") (class "Default")
      (node (ref "PCIE-NORTH") (pin "B13") (pinfunction "VCC_B13") (pintype "passive"))
    )
    (net (code "179") (name "N_VCCIO") (class "Default")
      (node (ref "PCIE-NORTH") (pin "B14") (pinfunction "VCCIO_B14") (pintype "passive"))
    )
    (net (code "180") (name "Net-(C5-Pad1)") (class "Default")
      (node (ref "C5") (pin "1") (pinfunction "1_1") (pintype "passive"))
      (node (ref "SDI-IN") (pin "1") (pinfunction "1_1") (pintype "passive"))
    )
    (net (code "181") (name "Net-(C7-Pad2)") (class "Default")
      (node (ref "C7") (pin "2") (pinfunction "2_2") (pintype "passive"))
      (node (ref "R10") (pin "1") (pinfunction "1_1") (pintype "passive"))
    )
    (net (code "182") (name "Net-(C20-Pad2)") (class "Default")
      (node (ref "C20") (pin "2") (pinfunction "2_2") (pintype "passive"))
      (node (ref "OUT1") (pin "1") (pinfunction "1_1") (pintype "passive"))
    )
    (net (code "183") (name "Net-(C21-Pad2)") (class "Default")
      (node (ref "C21") (pin "2") (pinfunction "2_2") (pintype "passive"))
      (node (ref "R11") (pin "1") (pinfunction "1_1") (pintype "passive"))
    )
    (net (code "184") (name "Net-(C22-Pad2)") (class "Default")
      (node (ref "C22") (pin "2") (pinfunction "2_2") (pintype "passive"))
      (node (ref "R12") (pin "1") (pinfunction "1_1") (pintype "passive"))
    )
    (net (code "185") (name "Net-(C23-Pad2)") (class "Default")
      (node (ref "C23") (pin "2") (pinfunction "2_2") (pintype "passive"))
      (node (ref "R13") (pin "1") (pinfunction "1_1") (pintype "passive"))
    )
    (net (code "186") (name "Net-(C38-Pad2)") (class "Default")
      (node (ref "C38") (pin "2") (pinfunction "2_2") (pintype "passive"))
      (node (ref "OUT2") (pin "1") (pinfunction "1_1") (pintype "passive"))
    )
    (net (code "187") (name "Net-(C39-Pad2)") (class "Default")
      (node (ref "C39") (pin "2") (pinfunction "2_2") (pintype "passive"))
      (node (ref "R14") (pin "1") (pinfunction "1_1") (pintype "passive"))
    )
    (net (code "188") (name "Net-(C40-Pad2)") (class "Default")
      (node (ref "C40") (pin "2") (pinfunction "2_2") (pintype "passive"))
      (node (ref "R15") (pin "1") (pinfunction "1_1") (pintype "passive"))
    )
    (net (code "189") (name "Net-(C41-Pad2)") (class "Default")
      (node (ref "C41") (pin "2") (pinfunction "2_2") (pintype "passive"))
      (node (ref "R16") (pin "1") (pinfunction "1_1") (pintype "passive"))
    )
    (net (code "190") (name "Net-(D1-PadC)") (class "Default")
      (node (ref "D1") (pin "C") (pinfunction "C_C") (pintype "passive"))
      (node (ref "R6") (pin "2") (pinfunction "2_2") (pintype "passive"))
    )
    (net (code "191") (name "Net-(D2-PadC)") (class "Default")
      (node (ref "D2") (pin "C") (pinfunction "C_C") (pintype "passive"))
      (node (ref "R7") (pin "2") (pinfunction "2_2") (pintype "passive"))
    )
    (net (code "192") (name "Net-(D3-PadC)") (class "Default")
      (node (ref "D3") (pin "C") (pinfunction "C_C") (pintype "passive"))
      (node (ref "R8") (pin "2") (pinfunction "2_2") (pintype "passive"))
    )
    (net (code "193") (name "Net-(D4-PadC)") (class "Default")
      (node (ref "D4") (pin "C") (pinfunction "C_C") (pintype "passive"))
      (node (ref "R9") (pin "2") (pinfunction "2_2") (pintype "passive"))
    )
    (net (code "194") (name "Net-(U1-OUT+)") (class "Default")
      (node (ref "C2") (pin "1") (pinfunction "1_1") (pintype "passive"))
      (node (ref "R1") (pin "1") (pinfunction "1_1") (pintype "passive"))
      (node (ref "U1") (pin "4") (pinfunction "OUT+_4") (pintype "output"))
    )
    (net (code "195") (name "Net-(U1-OUT-)") (class "Default")
      (node (ref "C3") (pin "1") (pinfunction "1_1") (pintype "passive"))
      (node (ref "R1") (pin "2") (pinfunction "2_2") (pintype "passive"))
      (node (ref "U1") (pin "5") (pinfunction "OUT-_5") (pintype "output"))
    )
    (net (code "196") (name "Net-(U2-WP)") (class "Default")
      (node (ref "R2") (pin "2") (pinfunction "2_2") (pintype "passive"))
      (node (ref "R3") (pin "1") (pinfunction "1_1") (pintype "passive"))
      (node (ref "U2") (pin "7") (pinfunction "WP_7") (pintype "input"))
    )
    (net (code "197") (name "Net-(U3-LF+)") (class "Default")
      (node (ref "C6") (pin "1") (pinfunction "1_1") (pintype "passive"))
      (node (ref "U3") (pin "39") (pinfunction "LF+_39") (pintype "passive"))
    )
    (net (code "198") (name "Net-(U3-LF-)") (class "Default")
      (node (ref "C6") (pin "2") (pinfunction "2_2") (pintype "passive"))
      (node (ref "U3") (pin "40") (pinfunction "LF-_40") (pintype "passive"))
    )
    (net (code "199") (name "Net-(U3-SDI)") (class "Default")
      (node (ref "C5") (pin "2") (pinfunction "2_2") (pintype "passive"))
      (node (ref "U3") (pin "2") (pinfunction "SDI_2") (pintype "input"))
    )
    (net (code "200") (name "Net-(U3-SDI_TERM)") (class "Default")
      (node (ref "C7") (pin "1") (pinfunction "1_1") (pintype "passive"))
      (node (ref "U3") (pin "3") (pinfunction "SDI_TERM_3") (pintype "passive"))
    )
    (net (code "201") (name "Net-(U3-VCO_FILT)") (class "Default")
      (node (ref "C8") (pin "1") (pinfunction "1_1") (pintype "passive"))
      (node (ref "U3") (pin "34") (pinfunction "VCO_FILT_34") (pintype "passive"))
    )
    (net (code "202") (name "Net-(U3-VCO_FILT10)") (class "Default")
      (node (ref "C9") (pin "1") (pinfunction "1_1") (pintype "passive"))
      (node (ref "U3") (pin "30") (pinfunction "VCO_FILT10_30") (pintype "passive"))
    )
    (net (code "203") (name "Net-(U4-LF+)") (class "Default")
      (node (ref "C24") (pin "1") (pinfunction "1_1") (pintype "passive"))
      (node (ref "U4") (pin "39") (pinfunction "LF+_39") (pintype "passive"))
    )
    (net (code "204") (name "Net-(U4-LF-)") (class "Default")
      (node (ref "C24") (pin "2") (pinfunction "2_2") (pintype "passive"))
      (node (ref "U4") (pin "40") (pinfunction "LF-_40") (pintype "passive"))
    )
    (net (code "205") (name "Net-(U4-SDO0)") (class "Default")
      (node (ref "C20") (pin "1") (pinfunction "1_1") (pintype "passive"))
      (node (ref "U4") (pin "27") (pinfunction "SDO0_27") (pintype "output"))
    )
    (net (code "206") (name "Net-(U4-SDO1{slash}RCO)") (class "Default")
      (node (ref "C22") (pin "1") (pinfunction "1_1") (pintype "passive"))
      (node (ref "U4") (pin "23") (pinfunction "SDO1/RCO_23") (pintype "output"))
    )
    (net (code "207") (name "Net-(U4-TERM)") (class "Default")
      (node (ref "C25") (pin "1") (pinfunction "1_1") (pintype "passive"))
      (node (ref "U4") (pin "5") (pinfunction "TERM_5") (pintype "passive"))
    )
    (net (code "208") (name "Net-(U4-VCO_FILT)") (class "Default")
      (node (ref "C26") (pin "1") (pinfunction "1_1") (pintype "passive"))
      (node (ref "U4") (pin "34") (pinfunction "VCO_FILT_34") (pintype "passive"))
    )
    (net (code "209") (name "Net-(U4-VCO_FILT10)") (class "Default")
      (node (ref "C27") (pin "1") (pinfunction "1_1") (pintype "passive"))
      (node (ref "U4") (pin "30") (pinfunction "VCO_FILT10_30") (pintype "passive"))
    )
    (net (code "210") (name "Net-(U4-~{SDO0})") (class "Default")
      (node (ref "C23") (pin "1") (pinfunction "1_1") (pintype "passive"))
      (node (ref "U4") (pin "26") (pinfunction "~{SDO0}_26") (pintype "output"))
    )
    (net (code "211") (name "Net-(U4-~{SDO1}{slash}~{RCO})") (class "Default")
      (node (ref "C21") (pin "1") (pinfunction "1_1") (pintype "passive"))
      (node (ref "U4") (pin "22") (pinfunction "~{SDO1}/~{RCO}_22") (pintype "output"))
    )
    (net (code "212") (name "Net-(U5-LF+)") (class "Default")
      (node (ref "C42") (pin "1") (pinfunction "1_1") (pintype "passive"))
      (node (ref "U5") (pin "39") (pinfunction "LF+_39") (pintype "passive"))
    )
    (net (code "213") (name "Net-(U5-LF-)") (class "Default")
      (node (ref "C42") (pin "2") (pinfunction "2_2") (pintype "passive"))
      (node (ref "U5") (pin "40") (pinfunction "LF-_40") (pintype "passive"))
    )
    (net (code "214") (name "Net-(U5-SDO0)") (class "Default")
      (node (ref "C41") (pin "1") (pinfunction "1_1") (pintype "passive"))
      (node (ref "U5") (pin "27") (pinfunction "SDO0_27") (pintype "output"))
    )
    (net (code "215") (name "Net-(U5-SDO1{slash}RCO)") (class "Default")
      (node (ref "C38") (pin "1") (pinfunction "1_1") (pintype "passive"))
      (node (ref "U5") (pin "23") (pinfunction "SDO1/RCO_23") (pintype "output"))
    )
    (net (code "216") (name "Net-(U5-TERM)") (class "Default")
      (node (ref "C43") (pin "1") (pinfunction "1_1") (pintype "passive"))
      (node (ref "U5") (pin "5") (pinfunction "TERM_5") (pintype "passive"))
    )
    (net (code "217") (name "Net-(U5-VCO_FILT)") (class "Default")
      (node (ref "C44") (pin "1") (pinfunction "1_1") (pintype "passive"))
      (node (ref "U5") (pin "34") (pinfunction "VCO_FILT_34") (pintype "passive"))
    )
    (net (code "218") (name "Net-(U5-VCO_FILT10)") (class "Default")
      (node (ref "C45") (pin "1") (pinfunction "1_1") (pintype "passive"))
      (node (ref "U5") (pin "30") (pinfunction "VCO_FILT10_30") (pintype "passive"))
    )
    (net (code "219") (name "Net-(U5-~{SDO0})") (class "Default")
      (node (ref "C40") (pin "1") (pinfunction "1_1") (pintype "passive"))
      (node (ref "U5") (pin "26") (pinfunction "~{SDO0}_26") (pintype "output"))
    )
    (net (code "220") (name "Net-(U5-~{SDO1}{slash}~{RCO})") (class "Default")
      (node (ref "C39") (pin "1") (pinfunction "1_1") (pintype "passive"))
      (node (ref "U5") (pin "22") (pinfunction "~{SDO1}/~{RCO}_22") (pintype "output"))
    )
    (net (code "221") (name "Net-(U6-FB)") (class "Default")
      (node (ref "R17") (pin "1") (pinfunction "1_1") (pintype "passive"))
      (node (ref "R18") (pin "2") (pinfunction "2_2") (pintype "passive"))
      (node (ref "U6") (pin "7") (pinfunction "FB_7") (pintype "output"))
    )
    (net (code "222") (name "Net-(U7-FB)") (class "Default")
      (node (ref "R19") (pin "1") (pinfunction "1_1") (pintype "passive"))
      (node (ref "R20") (pin "2") (pinfunction "2_2") (pintype "passive"))
      (node (ref "U7") (pin "7") (pinfunction "FB_7") (pintype "output"))
    )
    (net (code "223") (name "PROG_B") (class "Default")
      (node (ref "JM1") (pin "94") (pinfunction "94_94") (pintype "bidirectional"))
    )
    (net (code "224") (name "SCL") (class "Default")
      (node (ref "PCIE-NORTH") (pin "B2") (pinfunction "SCL_B2") (pintype "passive"))
      (node (ref "U2") (pin "6") (pinfunction "SCL_6") (pintype "input"))
    )
    (net (code "225") (name "SDA") (class "Default")
      (node (ref "PCIE-NORTH") (pin "B1") (pinfunction "SDA_B1") (pintype "passive"))
      (node (ref "U2") (pin "5") (pinfunction "SDA_5") (pintype "bidirectional"))
    )
    (net (code "226") (name "SPI-CLK") (class "Default")
      (node (ref "JM2") (pin "67") (pinfunction "67_67") (pintype "bidirectional"))
    )
    (net (code "227") (name "SPI-CS") (class "Default")
      (node (ref "JM2") (pin "69") (pinfunction "69_69") (pintype "bidirectional"))
    )
    (net (code "228") (name "SPI-DQ0") (class "Default")
      (node (ref "JM2") (pin "68") (pinfunction "68_68") (pintype "bidirectional"))
    )
    (net (code "229") (name "SPI-DQ1") (class "Default")
      (node (ref "JM2") (pin "71") (pinfunction "71_71") (pintype "bidirectional"))
    )
    (net (code "230") (name "SPI-DQ2") (class "Default")
      (node (ref "JM2") (pin "73") (pinfunction "73_73") (pintype "bidirectional"))
    )
    (net (code "231") (name "SPI-DQ3") (class "Default")
      (node (ref "JM2") (pin "70") (pinfunction "70_70") (pintype "bidirectional"))
    )
    (net (code "232") (name "S_5V") (class "Default")
      (node (ref "JP2") (pin "1") (pinfunction "1_1") (pintype "passive"))
      (node (ref "PCIE-SOUTH") (pin "B12") (pinfunction "5V_B12") (pintype "passive"))
    )
    (net (code "233") (name "S_PCIE_V") (class "Default")
      (node (ref "PCIE-SOUTH") (pin "B13") (pinfunction "VCC_B13") (pintype "passive"))
    )
    (net (code "234") (name "S_VCCIO") (class "Default")
      (node (ref "JM2") (pin "54") (pinfunction "54_54") (pintype "bidirectional"))
      (node (ref "PCIE-SOUTH") (pin "B14") (pinfunction "VCCIO_B14") (pintype "passive"))
    )
    (net (code "235") (name "TCK") (class "Default")
      (node (ref "JM1") (pin "90") (pinfunction "90_90") (pintype "bidirectional"))
      (node (ref "JTAG") (pin "6") (pinfunction "6_6") (pintype "passive"))
    )
    (net (code "236") (name "TDI") (class "Default")
      (node (ref "JM1") (pin "86") (pinfunction "86_86") (pintype "bidirectional"))
      (node (ref "JTAG") (pin "10") (pinfunction "10_10") (pintype "passive"))
    )
    (net (code "237") (name "TDO") (class "Default")
      (node (ref "JM1") (pin "88") (pinfunction "88_88") (pintype "bidirectional"))
      (node (ref "JTAG") (pin "8") (pinfunction "8_8") (pintype "passive"))
    )
    (net (code "238") (name "TMS") (class "Default")
      (node (ref "JM1") (pin "92") (pinfunction "92_92") (pintype "bidirectional"))
      (node (ref "JTAG") (pin "4") (pinfunction "4_4") (pintype "passive"))
    )
    (net (code "239") (name "VCCIO0") (class "Default")
      (node (ref "JM2") (pin "53") (pinfunction "53_53") (pintype "bidirectional"))
      (node (ref "JTAG") (pin "2") (pinfunction "2_2") (pintype "passive"))
    )
    (net (code "240") (name "VCCIO14") (class "Default")
      (node (ref "JM1") (pin "83") (pinfunction "83_83") (pintype "bidirectional"))
    )
    (net (code "241") (name "VCCO_4") (class "Default")
      (node (ref "C17") (pin "1") (pinfunction "1_1") (pintype "passive"))
      (node (ref "C18") (pin "1") (pinfunction "1_1") (pintype "passive"))
      (node (ref "C19") (pin "1") (pinfunction "1_1") (pintype "passive"))
      (node (ref "FB4") (pin "2") (pinfunction "2_2") (pintype "passive"))
      (node (ref "U3") (pin "24") (pinfunction "VCCO_1_24") (pintype "power_in"))
      (node (ref "U3") (pin "25") (pinfunction "VCCO_0_25") (pintype "power_in"))
    )
    (net (code "242") (name "VCCO_8") (class "Default")
      (node (ref "C35") (pin "1") (pinfunction "1_1") (pintype "passive"))
      (node (ref "C36") (pin "1") (pinfunction "1_1") (pintype "passive"))
      (node (ref "C37") (pin "1") (pinfunction "1_1") (pintype "passive"))
      (node (ref "FB7") (pin "2") (pinfunction "2_2") (pintype "passive"))
      (node (ref "U4") (pin "24") (pinfunction "VCCO_1_24") (pintype "power_in"))
      (node (ref "U4") (pin "25") (pinfunction "VCCO_0_25") (pintype "power_in"))
    )
    (net (code "243") (name "VCCO_9") (class "Default")
      (node (ref "C53") (pin "1") (pinfunction "1_1") (pintype "passive"))
      (node (ref "C54") (pin "1") (pinfunction "1_1") (pintype "passive"))
      (node (ref "C55") (pin "1") (pinfunction "1_1") (pintype "passive"))
      (node (ref "FB10") (pin "2") (pinfunction "2_2") (pintype "passive"))
      (node (ref "U5") (pin "24") (pinfunction "VCCO_1_24") (pintype "power_in"))
      (node (ref "U5") (pin "25") (pinfunction "VCCO_0_25") (pintype "power_in"))
    )
    (net (code "244") (name "VCC_4") (class "Default")
      (node (ref "C14") (pin "1") (pinfunction "1_1") (pintype "passive"))
      (node (ref "C15") (pin "1") (pinfunction "1_1") (pintype "passive"))
      (node (ref "C16") (pin "1") (pinfunction "1_1") (pintype "passive"))
      (node (ref "FB3") (pin "2") (pinfunction "2_2") (pintype "passive"))
      (node (ref "U3") (pin "35") (pinfunction "VCC_CORE_35") (pintype "power_in"))
      (node (ref "U3") (pin "4") (pinfunction "VCC_SDI_4") (pintype "power_in"))
    )
    (net (code "245") (name "VCC_8") (class "Default")
      (node (ref "C32") (pin "1") (pinfunction "1_1") (pintype "passive"))
      (node (ref "C33") (pin "1") (pinfunction "1_1") (pintype "passive"))
      (node (ref "C34") (pin "1") (pinfunction "1_1") (pintype "passive"))
      (node (ref "FB6") (pin "2") (pinfunction "2_2") (pintype "passive"))
      (node (ref "U4") (pin "35") (pinfunction "VCC_CORE_35") (pintype "power_in"))
      (node (ref "U4") (pin "4") (pinfunction "VCC_DDI_4") (pintype "power_in"))
    )
    (net (code "246") (name "VCC_9") (class "Default")
      (node (ref "C50") (pin "1") (pinfunction "1_1") (pintype "passive"))
      (node (ref "C51") (pin "1") (pinfunction "1_1") (pintype "passive"))
      (node (ref "C52") (pin "1") (pinfunction "1_1") (pintype "passive"))
      (node (ref "FB9") (pin "2") (pinfunction "2_2") (pintype "passive"))
      (node (ref "U5") (pin "35") (pinfunction "VCC_CORE_35") (pintype "power_in"))
      (node (ref "U5") (pin "4") (pinfunction "VCC_DDI_4") (pintype "power_in"))
    )
    (net (code "247") (name "VDD_4") (class "Default")
      (node (ref "C10") (pin "1") (pinfunction "1_1") (pintype "passive"))
      (node (ref "C11") (pin "1") (pinfunction "1_1") (pintype "passive"))
      (node (ref "C12") (pin "1") (pinfunction "1_1") (pintype "passive"))
      (node (ref "C13") (pin "1") (pinfunction "1_1") (pintype "passive"))
      (node (ref "FB2") (pin "2") (pinfunction "2_2") (pintype "passive"))
      (node (ref "U3") (pin "16") (pinfunction "VDD_16") (pintype "power_in"))
      (node (ref "U3") (pin "20") (pinfunction "VCCO1V8_1_20") (pintype "power_in"))
      (node (ref "U3") (pin "29") (pinfunction "VCCO1V8_0_29") (pintype "power_in"))
    )
    (net (code "248") (name "VDD_8") (class "Default")
      (node (ref "C28") (pin "1") (pinfunction "1_1") (pintype "passive"))
      (node (ref "C29") (pin "1") (pinfunction "1_1") (pintype "passive"))
      (node (ref "C30") (pin "1") (pinfunction "1_1") (pintype "passive"))
      (node (ref "C31") (pin "1") (pinfunction "1_1") (pintype "passive"))
      (node (ref "FB5") (pin "2") (pinfunction "2_2") (pintype "passive"))
      (node (ref "U4") (pin "16") (pinfunction "VDD_16") (pintype "power_in"))
      (node (ref "U4") (pin "20") (pinfunction "VCCO1V8_1_20") (pintype "power_in"))
      (node (ref "U4") (pin "29") (pinfunction "VCCO1V8_0_29") (pintype "power_in"))
    )
    (net (code "249") (name "VDD_9") (class "Default")
      (node (ref "C46") (pin "1") (pinfunction "1_1") (pintype "passive"))
      (node (ref "C47") (pin "1") (pinfunction "1_1") (pintype "passive"))
      (node (ref "C48") (pin "1") (pinfunction "1_1") (pintype "passive"))
      (node (ref "C49") (pin "1") (pinfunction "1_1") (pintype "passive"))
      (node (ref "FB8") (pin "2") (pinfunction "2_2") (pintype "passive"))
      (node (ref "U5") (pin "16") (pinfunction "VDD_16") (pintype "power_in"))
      (node (ref "U5") (pin "20") (pinfunction "VCCO1V8_1_20") (pintype "power_in"))
      (node (ref "U5") (pin "29") (pinfunction "VCCO1V8_0_29") (pintype "power_in"))
    )
    (net (code "250") (name "VOUT_A") (class "Default")
      (node (ref "C57") (pin "1") (pinfunction "1_1") (pintype "passive"))
      (node (ref "FB11") (pin "1") (pinfunction "1_1") (pintype "passive"))
      (node (ref "R17") (pin "2") (pinfunction "2_2") (pintype "passive"))
      (node (ref "U6") (pin "8") (pinfunction "VOUT_8") (pintype "output"))
    )
    (net (code "251") (name "VOUT_B") (class "Default")
      (node (ref "C59") (pin "1") (pinfunction "1_1") (pintype "passive"))
      (node (ref "FB12") (pin "1") (pinfunction "1_1") (pintype "passive"))
      (node (ref "R19") (pin "2") (pinfunction "2_2") (pintype "passive"))
      (node (ref "U7") (pin "8") (pinfunction "VOUT_8") (pintype "output"))
    )
    (net (code "252") (name "VSUP") (class "Default")
      (node (ref "C56") (pin "1") (pinfunction "1_1") (pintype "passive"))
      (node (ref "C58") (pin "1") (pinfunction "1_1") (pintype "passive"))
      (node (ref "JP2") (pin "2") (pinfunction "2_2") (pintype "passive"))
      (node (ref "R21") (pin "2") (pinfunction "2_2") (pintype "passive"))
      (node (ref "R99") (pin "2") (pinfunction "2_2") (pintype "passive"))
      (node (ref "U6") (pin "3") (pinfunction "VIN_3") (pintype "power_in"))
      (node (ref "U6") (pin "4") (pinfunction "VIN_4") (pintype "power_in"))
      (node (ref "U7") (pin "3") (pinfunction "VIN_3") (pintype "power_in"))
      (node (ref "U7") (pin "4") (pinfunction "VIN_4") (pintype "power_in"))
    )
    (net (code "253") (name "VXX") (class "Default")
      (node (ref "C1") (pin "1") (pinfunction "1_1") (pintype "passive"))
      (node (ref "FB1") (pin "2") (pinfunction "2_2") (pintype "passive"))
      (node (ref "U1") (pin "6") (pinfunction "VCC_6") (pintype "power_in"))
    )
    (net (code "254") (name "unconnected-(JTAG-Pad12)") (class "Default")
      (node (ref "JTAG") (pin "12") (pinfunction "12_12") (pintype "passive"))
    )
    (net (code "255") (name "unconnected-(JTAG-Pad14)") (class "Default")
      (node (ref "JTAG") (pin "14") (pinfunction "14_14") (pintype "passive"))
    )
    (net (code "256") (name "unconnected-(PCIE-NORTH-PWRGD-PadA11)") (class "Default")
      (node (ref "PCIE-NORTH") (pin "A11") (pinfunction "PWRGD_A11") (pintype "passive"))
    )
    (net (code "257") (name "unconnected-(PCIE-SOUTH-PWRGD-PadA11)") (class "Default")
      (node (ref "PCIE-SOUTH") (pin "A11") (pinfunction "PWRGD_A11") (pintype "passive"))
    )
    (net (code "258") (name "unconnected-(PCIE-SOUTH-SCL-PadB2)") (class "Default")
      (node (ref "PCIE-SOUTH") (pin "B2") (pinfunction "SCL_B2") (pintype "passive"))
    )
    (net (code "259") (name "unconnected-(PCIE-SOUTH-SDA-PadB1)") (class "Default")
      (node (ref "PCIE-SOUTH") (pin "B1") (pinfunction "SDA_B1") (pintype "passive"))
    )
    (net (code "260") (name "unconnected-(PCIE-SOUTH-V_I2C-PadB3)") (class "Default")
      (node (ref "PCIE-SOUTH") (pin "B3") (pinfunction "V_I2C_B3") (pintype "passive"))
    )
  )
)
